# On_Board_Computer.net
KiCad netlist of a schematic drawn in EAGLE
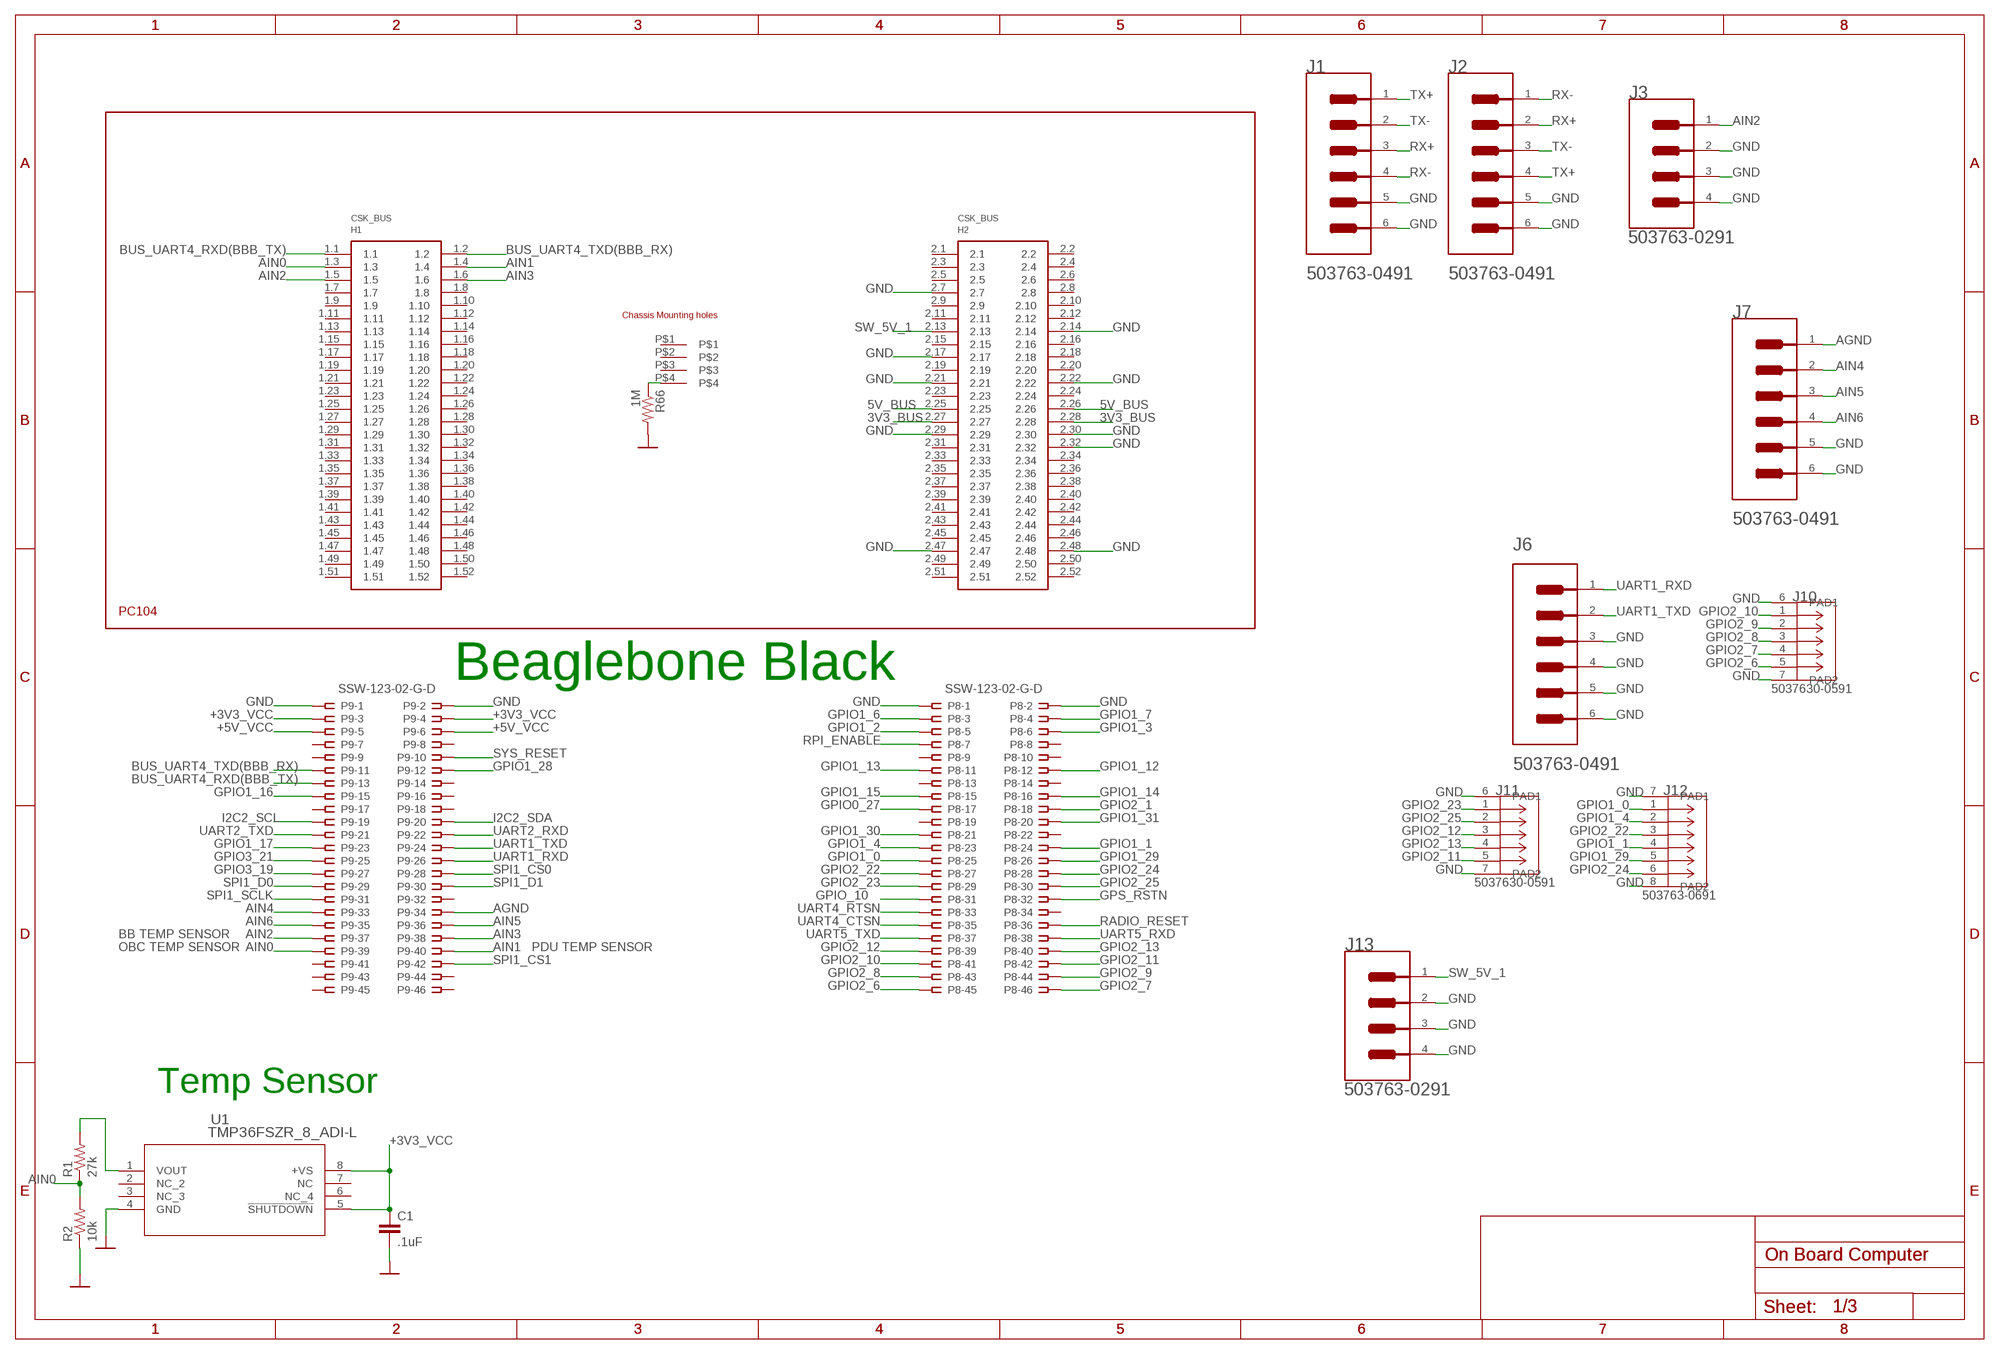
[diagram p0: schematic, sheet 1]
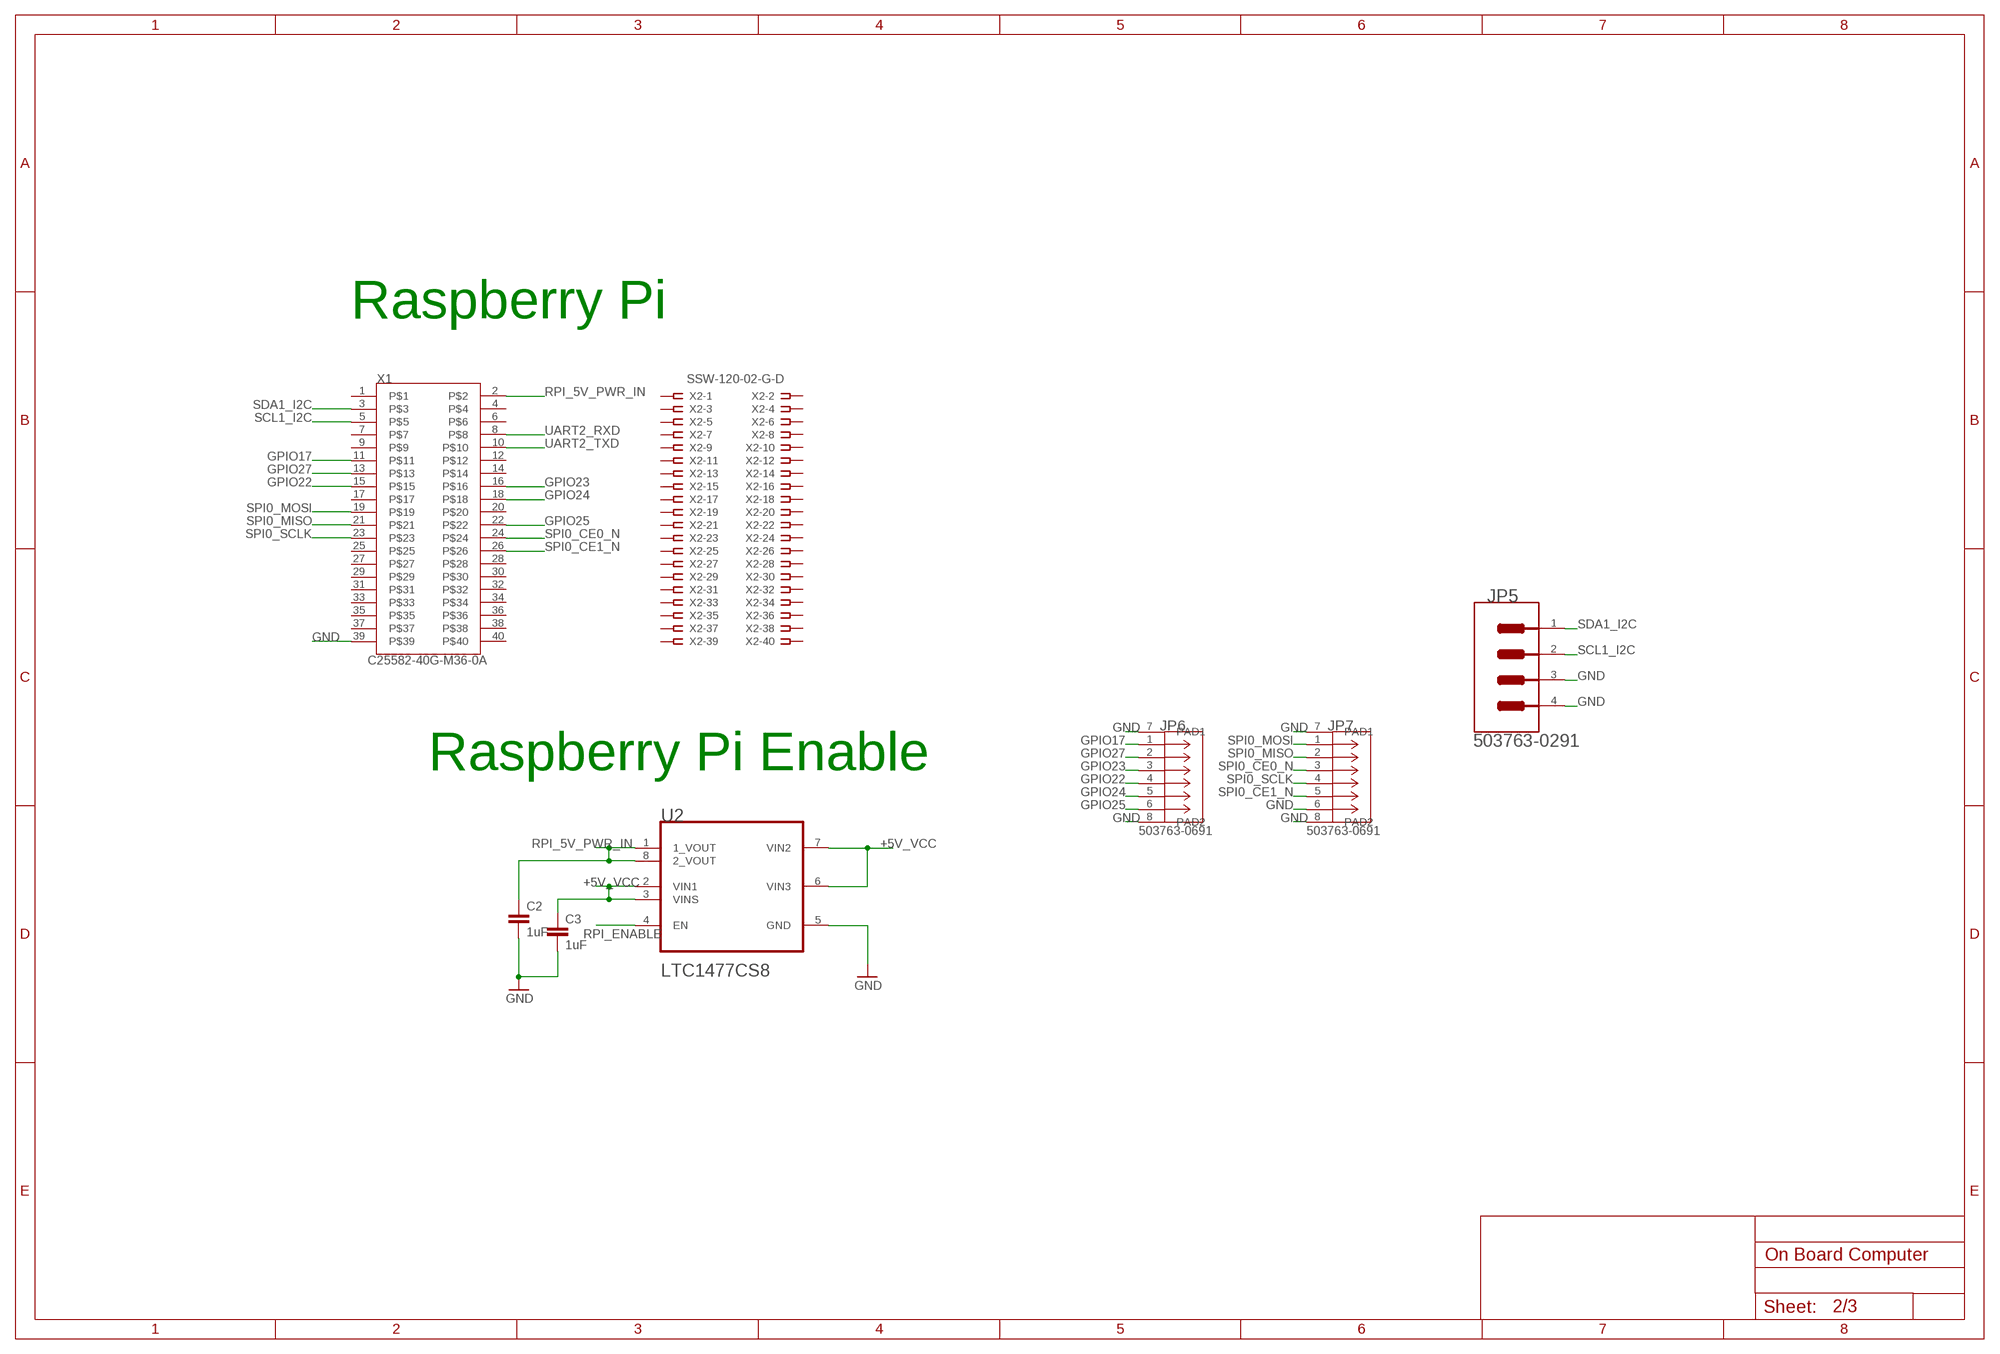
[diagram p1: schematic, sheet 2]
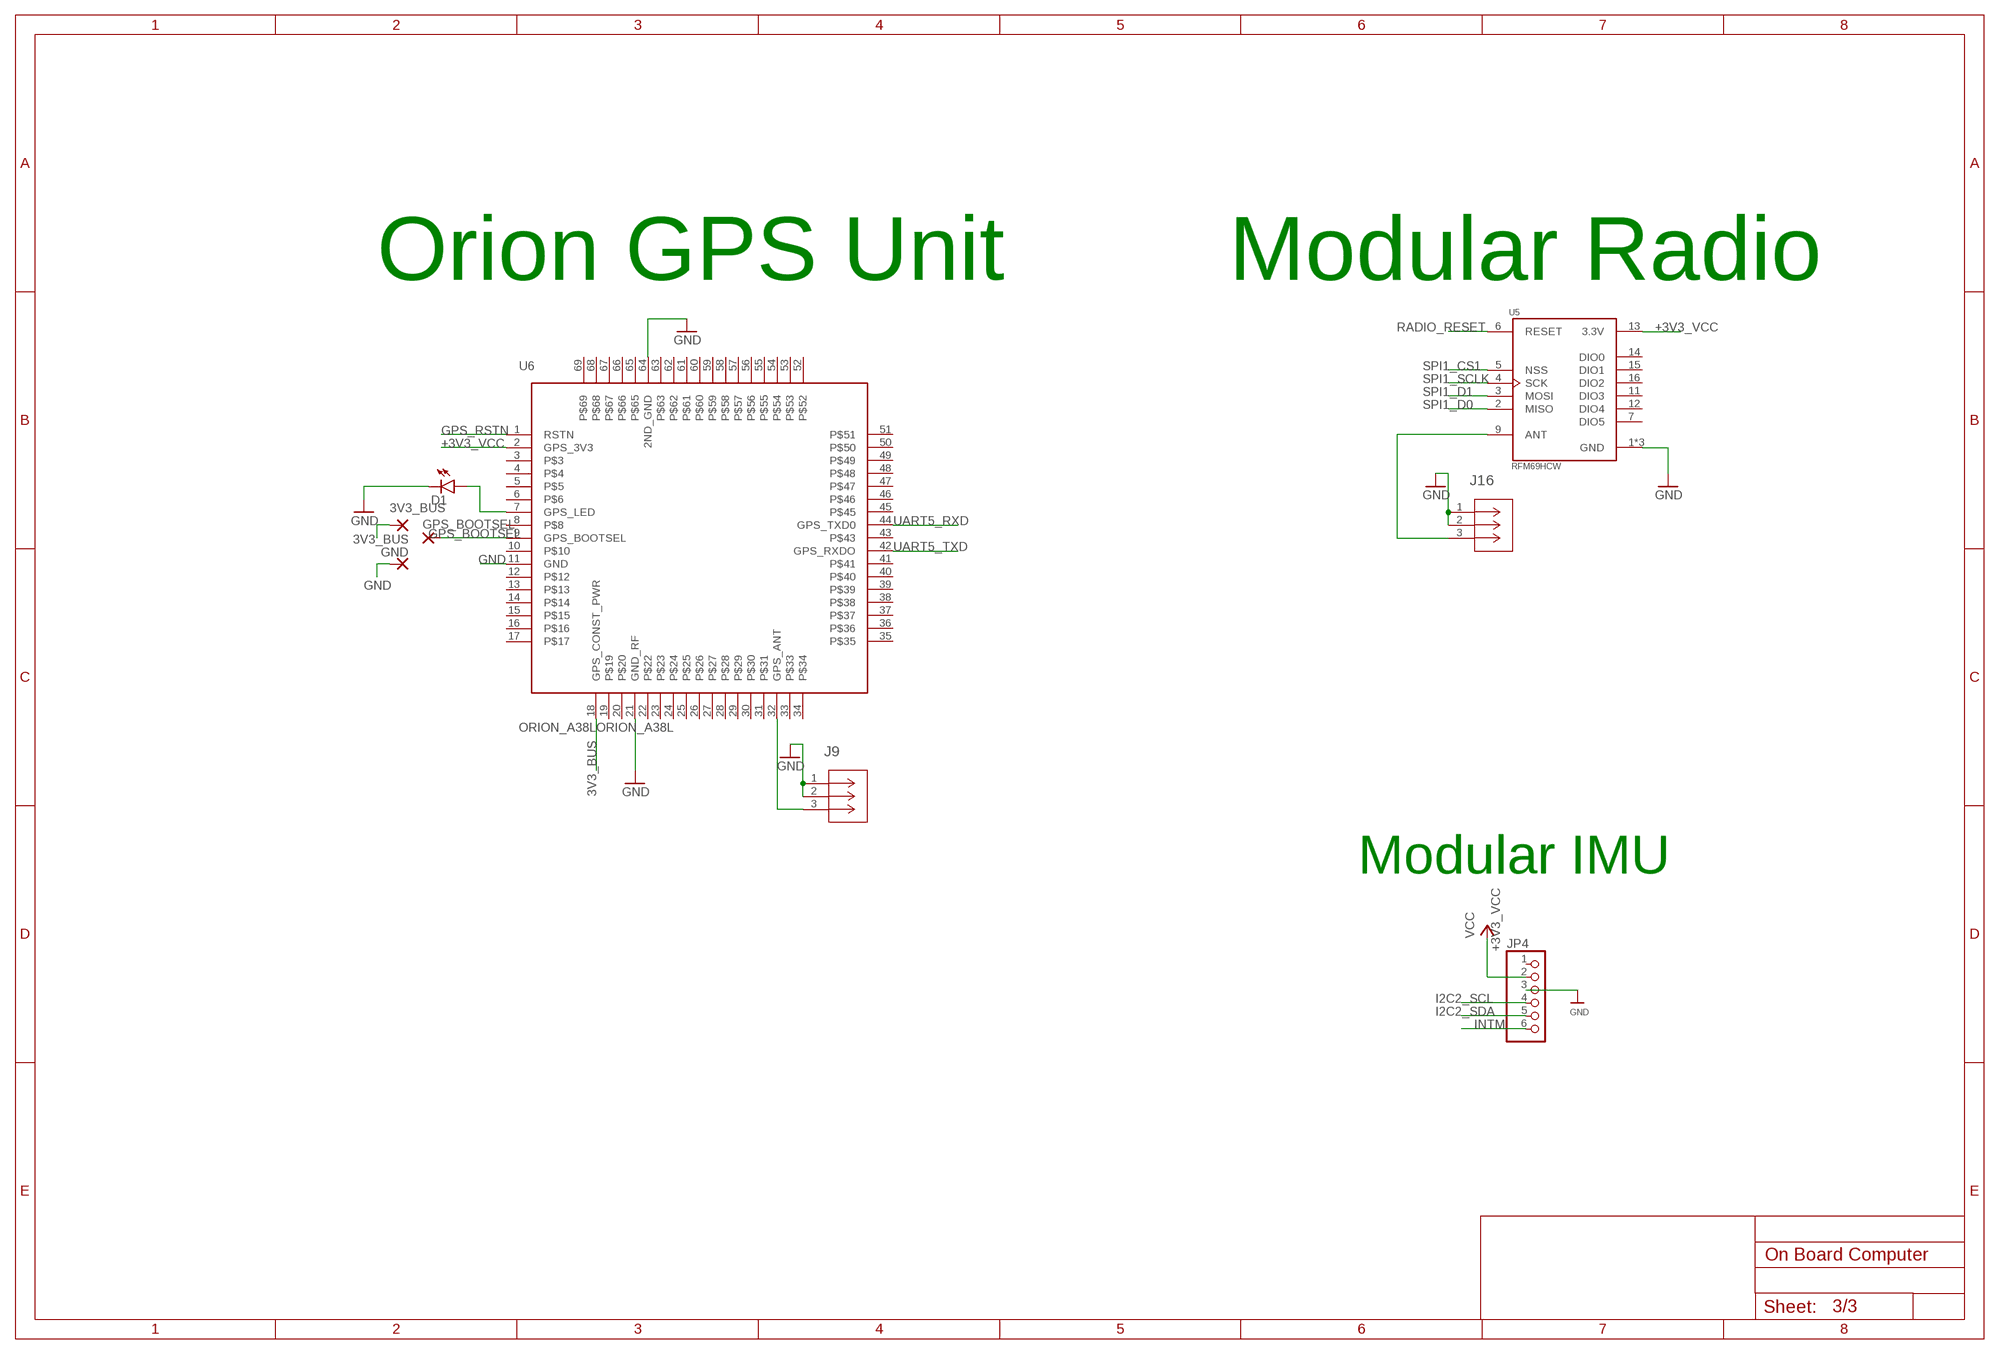
[diagram p2: schematic, sheet 3]

(export (version "E")
  (design (tool "Eeschema 10.0.6"))
  (components
    (comp (ref "3V3_BUS")
      (value "1,6/0,9")
      (footprint "eagle-import:1,6_0,9")
      (libsource (lib "eagle-import") (part "1,6/0,9"))
    )
    (comp (ref "D1")
      (value "LEDCHIP-LED0603")
      (footprint "eagle-import:CHIP-LED0603")
      (libsource (lib "eagle-import") (part "LEDCHIP-LED0603"))
    )
    (comp (ref "GND")
      (value "GND")
      (footprint "eagle-import:1,6_0,9")
      (libsource (lib "eagle-import") (part "1,6/0,9"))
    )
    (comp (ref "GPS_BOOTSEL")
      (value "1,6/0,9")
      (footprint "eagle-import:1,6_0,9")
      (libsource (lib "eagle-import") (part "1,6/0,9"))
    )
    (comp (ref "J9")
      (value "U.FL-R-SMT-1(01)")
      (footprint "eagle-import:CONN_-SMT-1(01)")
      (fields (field (name "COPYRIGHT") "Copyright (C) 2018 Accelerated Designs. All rights reserved"))
      (libsource (lib "eagle-import") (part "U.FL-R-SMT-1(01)"))
    )
    (comp (ref "J16")
      (value "U.FL-R-SMT-1(01)")
      (footprint "eagle-import:CONN_-SMT-1(01)")
      (fields (field (name "COPYRIGHT") "Copyright (C) 2018 Accelerated Designs. All rights reserved"))
      (libsource (lib "eagle-import") (part "U.FL-R-SMT-1(01)"))
    )
    (comp (ref "JP4")
      (value "HEADER-1X670MIL")
      (footprint "eagle-import:1X06_ROUND_70")
      (libsource (lib "eagle-import") (part "HEADER-1X670MIL"))
    )
    (comp (ref "U5")
      (value "RFM69HCW")
      (footprint "eagle-import:RFM69HCW")
      (fields (field (name "MF") "HOPERF") (field (name "MP") "RFM69HCW-315S2"))
      (libsource (lib "eagle-import") (part "RFM69HCW"))
    )
    (comp (ref "U6")
      (value "ORION_A38LORION_A38L")
      (footprint "eagle-import:ORION_A38L")
      (libsource (lib "eagle-import") (part "ORION_A38LORION_A38L"))
    )
    (comp (ref "C2")
      (value "1uF")
      (footprint "eagle-import:0805")
      (libsource (lib "eagle-import") (part "CAP0805"))
    )
    (comp (ref "C3")
      (value "1uF")
      (footprint "eagle-import:0805")
      (libsource (lib "eagle-import") (part "CAP0805"))
    )
    (comp (ref "JP5")
      (value "MOLEX_503763-0291MOLEX_503763-0291_0_0")
      (footprint "eagle-import:MOLEX_503763-0291_0")
      (fields
        (field (name "DIGIKEY_PART_NUMBER") "WM10654CT-ND")
        (field (name "MF") "Molex")
        (field (name "MOUSER_PART_NUMBER") "538-503763-0291")
      )
      (libsource (lib "eagle-import") (part "MOLEX_503763-0291MOLEX_503763-0291_0_0"))
    )
    (comp (ref "JP6")
      (value "503763-0691")
      (footprint "eagle-import:CONN_503763-0691_MOL")
      (fields (field (name "COPYRIGHT") "Copyright (C) 2018 Accelerated Designs. All rights reserved"))
      (libsource (lib "eagle-import") (part "503763-0691"))
    )
    (comp (ref "JP7")
      (value "503763-0691")
      (footprint "eagle-import:CONN_503763-0691_MOL")
      (fields (field (name "COPYRIGHT") "Copyright (C) 2018 Accelerated Designs. All rights reserved"))
      (libsource (lib "eagle-import") (part "503763-0691"))
    )
    (comp (ref "U2")
      (value "LTC1477CS8LINEAR_TECHNOLOGY_LTC1477CS8_0_2")
      (footprint "eagle-import:LINEAR_TECHNOLOGY_LTC1477CS8_2")
      (fields (field (name "MF") "Linear Technology") (field (name "MPN") "LTC1477CS8"))
      (libsource (lib "eagle-import") (part "LTC1477CS8LINEAR_TECHNOLOGY_LTC1477CS8_0_2"))
    )
    (comp (ref "X1")
      (value "C25582-40G-M36-0A")
      (footprint "eagle-import:ADAFRUIT_C25582-40G-M36-0A_0")
      (libsource (lib "eagle-import") (part "C25582-40G-M36-0A"))
    )
    (comp (ref "X2")
      (value "SSW-120-02-G-D")
      (footprint "eagle-import:SSW-120-02-G-D")
      (fields (field (name "MF") "Samtec Inc."))
      (libsource (lib "eagle-import") (part "SSW-120-02-G-D"))
    )
    (comp (ref "C1")
      (value ".1uF")
      (footprint "eagle-import:0805")
      (libsource (lib "eagle-import") (part "CAP0805"))
    )
    (comp (ref "H1")
      (value "PC104_WCONN")
      (footprint "eagle-import:PC104_WCONN")
      (libsource (lib "eagle-import") (part "PC104_WCONN"))
    )
    (comp (ref "J1")
      (value "MOLEX_503763-0491MOLEX_503763-0491_0_0")
      (footprint "eagle-import:MOLEX_503763-0491_0")
      (fields
        (field (name "DIGIKEY_PART_NUMBER") "WM10655CT-ND")
        (field (name "MF") "Molex")
        (field (name "MOUSER_PART_NUMBER") "538-503763-0491")
      )
      (libsource (lib "eagle-import") (part "MOLEX_503763-0491MOLEX_503763-0491_0_0"))
    )
    (comp (ref "J2")
      (value "MOLEX_503763-0491MOLEX_503763-0491_0_0")
      (footprint "eagle-import:MOLEX_503763-0491_0")
      (fields
        (field (name "DIGIKEY_PART_NUMBER") "WM10655CT-ND")
        (field (name "MF") "Molex")
        (field (name "MOUSER_PART_NUMBER") "538-503763-0491")
      )
      (libsource (lib "eagle-import") (part "MOLEX_503763-0491MOLEX_503763-0491_0_0"))
    )
    (comp (ref "J3")
      (value "MOLEX_503763-0291MOLEX_503763-0291_0_0")
      (footprint "eagle-import:MOLEX_503763-0291_0")
      (fields
        (field (name "DIGIKEY_PART_NUMBER") "WM10654CT-ND")
        (field (name "MF") "Molex")
        (field (name "MOUSER_PART_NUMBER") "538-503763-0291")
      )
      (libsource (lib "eagle-import") (part "MOLEX_503763-0291MOLEX_503763-0291_0_0"))
    )
    (comp (ref "J6")
      (value "MOLEX_503763-0491MOLEX_503763-0491_0_0")
      (footprint "eagle-import:MOLEX_503763-0491_0")
      (fields
        (field (name "DIGIKEY_PART_NUMBER") "WM10655CT-ND")
        (field (name "MF") "Molex")
        (field (name "MOUSER_PART_NUMBER") "538-503763-0491")
      )
      (libsource (lib "eagle-import") (part "MOLEX_503763-0491MOLEX_503763-0491_0_0"))
    )
    (comp (ref "J7")
      (value "MOLEX_503763-0491MOLEX_503763-0491_0_0")
      (footprint "eagle-import:MOLEX_503763-0491_0")
      (fields
        (field (name "DIGIKEY_PART_NUMBER") "WM10655CT-ND")
        (field (name "MF") "Molex")
        (field (name "MOUSER_PART_NUMBER") "538-503763-0491")
      )
      (libsource (lib "eagle-import") (part "MOLEX_503763-0491MOLEX_503763-0491_0_0"))
    )
    (comp (ref "J10")
      (value "503763-0591")
      (footprint "eagle-import:CONN_5037630591_MOL")
      (fields (field (name "COPYRIGHT") "Copyright (C) 2018 Accelerated Designs. All rights reserved"))
      (libsource (lib "eagle-import") (part "503763-0591"))
    )
    (comp (ref "J11")
      (value "503763-0591")
      (footprint "eagle-import:CONN_5037630591_MOL")
      (fields (field (name "COPYRIGHT") "Copyright (C) 2018 Accelerated Designs. All rights reserved"))
      (libsource (lib "eagle-import") (part "503763-0591"))
    )
    (comp (ref "J12")
      (value "503763-0691")
      (footprint "eagle-import:CONN_503763-0691_MOL")
      (fields (field (name "COPYRIGHT") "Copyright (C) 2018 Accelerated Designs. All rights reserved"))
      (libsource (lib "eagle-import") (part "503763-0691"))
    )
    (comp (ref "J13")
      (value "MOLEX_503763-0291MOLEX_503763-0291_0_0")
      (footprint "eagle-import:MOLEX_503763-0291_0")
      (fields
        (field (name "DIGIKEY_PART_NUMBER") "WM10654CT-ND")
        (field (name "MF") "Molex")
        (field (name "MOUSER_PART_NUMBER") "538-503763-0291")
      )
      (libsource (lib "eagle-import") (part "MOLEX_503763-0291MOLEX_503763-0291_0_0"))
    )
    (comp (ref "P8")
      (value "SSW-123-02-G-D")
      (footprint "eagle-import:SSW-123-02-G-D")
      (fields (field (name "MF") "Samtec Inc."))
      (libsource (lib "eagle-import") (part "SSW-123-02-G-D"))
    )
    (comp (ref "P9")
      (value "SSW-123-02-G-D")
      (footprint "eagle-import:SSW-123-02-G-D")
      (fields (field (name "MF") "Samtec Inc."))
      (libsource (lib "eagle-import") (part "SSW-123-02-G-D"))
    )
    (comp (ref "R1")
      (value "27k")
      (footprint "eagle-import:0805")
      (libsource (lib "eagle-import") (part "RESISTOR0805-RES"))
    )
    (comp (ref "R2")
      (value "10k")
      (footprint "eagle-import:0805")
      (libsource (lib "eagle-import") (part "RESISTOR0805-RES"))
    )
    (comp (ref "R66")
      (value "1M")
      (footprint "eagle-import:0805")
      (libsource (lib "eagle-import") (part "RESISTOR0805-RES"))
    )
    (comp (ref "U1")
      (value "TMP36FSZR_8_ADI-L")
      (footprint "eagle-import:R_8_ADI-L")
      (fields
        (field (name "MANUFACTURER_PART_NUMBER") "TMP36FSZ")
        (field (name "COPYRIGHT") "Copyright (C) 2021 Ultra Librarian. All rights reserved.")
      )
      (libsource (lib "eagle-import") (part "TMP36FSZR_8_ADI-L"))
    )
  )
  (nets
    (net (code "1") (name "+3V3_VCC") (class "Default")
      (node (ref "C1") (pin "1") (pinfunction "1_1") (pintype "passive"))
      (node (ref "JP4") (pin "2") (pinfunction "2_2") (pintype "passive"))
      (node (ref "P9") (pin "3") (pinfunction "1_3") (pintype "passive"))
      (node (ref "P9") (pin "4") (pinfunction "1_4") (pintype "passive"))
      (node (ref "U1") (pin "5") (pinfunction "~{SHUTDOWN}_5") (pintype "passive"))
      (node (ref "U1") (pin "8") (pinfunction "+VS_8") (pintype "power_in"))
      (node (ref "U5") (pin "13") (pinfunction "3.3V_13") (pintype "power_in"))
      (node (ref "U6") (pin "2") (pinfunction "GPS_3V3_2") (pintype "bidirectional"))
    )
    (net (code "2") (name "+5V_VCC") (class "Default")
      (node (ref "C3") (pin "1") (pinfunction "1_1") (pintype "passive"))
      (node (ref "P9") (pin "5") (pinfunction "1_5") (pintype "passive"))
      (node (ref "P9") (pin "6") (pinfunction "1_6") (pintype "passive"))
      (node (ref "U2") (pin "2") (pinfunction "VIN1_2") (pintype "power_in"))
      (node (ref "U2") (pin "3") (pinfunction "VINS_3") (pintype "power_in"))
      (node (ref "U2") (pin "6") (pinfunction "VIN3_6") (pintype "power_in"))
      (node (ref "U2") (pin "7") (pinfunction "VIN2_7") (pintype "power_in"))
    )
    (net (code "3") (name "3V3_BUS") (class "Default")
      (node (ref "3V3_BUS") (pin "1") (pinfunction "P_1") (pintype "passive"))
      (node (ref "H1") (pin "2.27") (pinfunction "2.27_2.27") (pintype "bidirectional"))
      (node (ref "H1") (pin "2.28") (pinfunction "2.28_2.28") (pintype "bidirectional"))
      (node (ref "U6") (pin "18") (pinfunction "GPS_CONST_PWR_18") (pintype "bidirectional"))
    )
    (net (code "4") (name "5V_BUS") (class "Default")
      (node (ref "H1") (pin "2.25") (pinfunction "2.25_2.25") (pintype "bidirectional"))
      (node (ref "H1") (pin "2.26") (pinfunction "2.26_2.26") (pintype "bidirectional"))
    )
    (net (code "5") (name "AGND") (class "Default")
      (node (ref "J7") (pin "1") (pinfunction "1_1") (pintype "passive"))
      (node (ref "P9") (pin "34") (pinfunction "1_34") (pintype "passive"))
    )
    (net (code "6") (name "AIN0") (class "Default")
      (node (ref "H1") (pin "1.3") (pinfunction "1.3_1.3") (pintype "bidirectional"))
      (node (ref "P9") (pin "39") (pinfunction "1_39") (pintype "passive"))
      (node (ref "R1") (pin "1") (pinfunction "1_1") (pintype "passive"))
      (node (ref "R2") (pin "2") (pinfunction "2_2") (pintype "passive"))
    )
    (net (code "7") (name "AIN1") (class "Default")
      (node (ref "H1") (pin "1.4") (pinfunction "1.4_1.4") (pintype "bidirectional"))
      (node (ref "P9") (pin "40") (pinfunction "1_40") (pintype "passive"))
    )
    (net (code "8") (name "AIN2") (class "Default")
      (node (ref "H1") (pin "1.5") (pinfunction "1.5_1.5") (pintype "bidirectional"))
      (node (ref "J3") (pin "1") (pinfunction "1_1") (pintype "bidirectional"))
      (node (ref "P9") (pin "37") (pinfunction "1_37") (pintype "passive"))
    )
    (net (code "9") (name "AIN3") (class "Default")
      (node (ref "H1") (pin "1.6") (pinfunction "1.6_1.6") (pintype "bidirectional"))
      (node (ref "P9") (pin "38") (pinfunction "1_38") (pintype "passive"))
    )
    (net (code "10") (name "AIN4") (class "Default")
      (node (ref "J7") (pin "2") (pinfunction "2_2") (pintype "passive"))
      (node (ref "P9") (pin "33") (pinfunction "1_33") (pintype "passive"))
    )
    (net (code "11") (name "AIN5") (class "Default")
      (node (ref "J7") (pin "3") (pinfunction "3_3") (pintype "passive"))
      (node (ref "P9") (pin "36") (pinfunction "1_36") (pintype "passive"))
    )
    (net (code "12") (name "AIN6") (class "Default")
      (node (ref "J7") (pin "4") (pinfunction "4_4") (pintype "passive"))
      (node (ref "P9") (pin "35") (pinfunction "1_35") (pintype "passive"))
    )
    (net (code "13") (name "BUS_UART4_RXD(BBB_TX)") (class "Default")
      (node (ref "H1") (pin "1.1") (pinfunction "1.1_1.1") (pintype "bidirectional"))
      (node (ref "P9") (pin "13") (pinfunction "1_13") (pintype "passive"))
    )
    (net (code "14") (name "BUS_UART4_TXD(BBB_RX)") (class "Default")
      (node (ref "H1") (pin "1.2") (pinfunction "1.2_1.2") (pintype "bidirectional"))
      (node (ref "P9") (pin "11") (pinfunction "1_11") (pintype "passive"))
    )
    (net (code "15") (name "GND") (class "Default")
      (node (ref "C1") (pin "2") (pinfunction "2_2") (pintype "passive"))
      (node (ref "C2") (pin "2") (pinfunction "2_2") (pintype "passive"))
      (node (ref "C3") (pin "2") (pinfunction "2_2") (pintype "passive"))
      (node (ref "D1") (pin "C") (pinfunction "C_C") (pintype "passive"))
      (node (ref "GND") (pin "1") (pinfunction "P_1") (pintype "passive"))
      (node (ref "H1") (pin "2.14") (pinfunction "2.14_2.14") (pintype "bidirectional"))
      (node (ref "H1") (pin "2.17") (pinfunction "2.17_2.17") (pintype "bidirectional"))
      (node (ref "H1") (pin "2.21") (pinfunction "2.21_2.21") (pintype "bidirectional"))
      (node (ref "H1") (pin "2.22") (pinfunction "2.22_2.22") (pintype "bidirectional"))
      (node (ref "H1") (pin "2.29") (pinfunction "2.29_2.29") (pintype "bidirectional"))
      (node (ref "H1") (pin "2.30") (pinfunction "2.30_2.30") (pintype "bidirectional"))
      (node (ref "H1") (pin "2.32") (pinfunction "2.32_2.32") (pintype "bidirectional"))
      (node (ref "H1") (pin "2.47") (pinfunction "2.47_2.47") (pintype "bidirectional"))
      (node (ref "H1") (pin "2.48") (pinfunction "2.48_2.48") (pintype "bidirectional"))
      (node (ref "H1") (pin "2.7") (pinfunction "2.7_2.7") (pintype "bidirectional"))
      (node (ref "J1") (pin "5") (pinfunction "MNT_1_5") (pintype "passive"))
      (node (ref "J1") (pin "6") (pinfunction "MNT_2_6") (pintype "passive"))
      (node (ref "J10") (pin "6") (pinfunction "PAD1_6") (pintype "bidirectional"))
      (node (ref "J10") (pin "7") (pinfunction "PAD2_7") (pintype "bidirectional"))
      (node (ref "J11") (pin "6") (pinfunction "PAD1_6") (pintype "bidirectional"))
      (node (ref "J11") (pin "7") (pinfunction "PAD2_7") (pintype "bidirectional"))
      (node (ref "J12") (pin "7") (pinfunction "PAD1_7") (pintype "bidirectional"))
      (node (ref "J12") (pin "8") (pinfunction "PAD2_8") (pintype "bidirectional"))
      (node (ref "J13") (pin "2") (pinfunction "2_2") (pintype "bidirectional"))
      (node (ref "J13") (pin "3") (pinfunction "MNT_1_3") (pintype "bidirectional"))
      (node (ref "J13") (pin "4") (pinfunction "MNT_2_4") (pintype "bidirectional"))
      (node (ref "J16") (pin "1") (pinfunction "1_1") (pintype "passive"))
      (node (ref "J16") (pin "2") (pinfunction "2_2") (pintype "passive"))
      (node (ref "J2") (pin "5") (pinfunction "MNT_1_5") (pintype "passive"))
      (node (ref "J2") (pin "6") (pinfunction "MNT_2_6") (pintype "passive"))
      (node (ref "J3") (pin "2") (pinfunction "2_2") (pintype "bidirectional"))
      (node (ref "J3") (pin "3") (pinfunction "MNT_1_3") (pintype "bidirectional"))
      (node (ref "J3") (pin "4") (pinfunction "MNT_2_4") (pintype "bidirectional"))
      (node (ref "J6") (pin "3") (pinfunction "3_3") (pintype "passive"))
      (node (ref "J6") (pin "4") (pinfunction "4_4") (pintype "passive"))
      (node (ref "J6") (pin "5") (pinfunction "MNT_1_5") (pintype "passive"))
      (node (ref "J6") (pin "6") (pinfunction "MNT_2_6") (pintype "passive"))
      (node (ref "J7") (pin "5") (pinfunction "MNT_1_5") (pintype "passive"))
      (node (ref "J7") (pin "6") (pinfunction "MNT_2_6") (pintype "passive"))
      (node (ref "J9") (pin "1") (pinfunction "1_1") (pintype "passive"))
      (node (ref "J9") (pin "2") (pinfunction "2_2") (pintype "passive"))
      (node (ref "JP4") (pin "3") (pinfunction "3_3") (pintype "passive"))
      (node (ref "JP5") (pin "3") (pinfunction "MNT_1_3") (pintype "bidirectional"))
      (node (ref "JP5") (pin "4") (pinfunction "MNT_2_4") (pintype "bidirectional"))
      (node (ref "JP6") (pin "7") (pinfunction "PAD1_7") (pintype "bidirectional"))
      (node (ref "JP6") (pin "8") (pinfunction "PAD2_8") (pintype "bidirectional"))
      (node (ref "JP7") (pin "6") (pinfunction "6_6") (pintype "passive"))
      (node (ref "JP7") (pin "7") (pinfunction "PAD1_7") (pintype "bidirectional"))
      (node (ref "JP7") (pin "8") (pinfunction "PAD2_8") (pintype "bidirectional"))
      (node (ref "P8") (pin "1") (pinfunction "1_1") (pintype "passive"))
      (node (ref "P8") (pin "2") (pinfunction "1_2") (pintype "passive"))
      (node (ref "P9") (pin "1") (pinfunction "1_1") (pintype "passive"))
      (node (ref "P9") (pin "2") (pinfunction "1_2") (pintype "passive"))
      (node (ref "R2") (pin "1") (pinfunction "1_1") (pintype "passive"))
      (node (ref "R66") (pin "2") (pinfunction "2_2") (pintype "passive"))
      (node (ref "U1") (pin "4") (pinfunction "GND_4") (pintype "passive"))
      (node (ref "U2") (pin "5") (pinfunction "GND_5") (pintype "power_in"))
      (node (ref "U5") (pin "1") (pinfunction "GND_1") (pintype "power_in"))
      (node (ref "U5") (pin "10") (pinfunction "GND_10") (pintype "power_in"))
      (node (ref "U5") (pin "8") (pinfunction "GND_8") (pintype "power_in"))
      (node (ref "U6") (pin "11") (pinfunction "GND_11") (pintype "bidirectional"))
      (node (ref "U6") (pin "21") (pinfunction "GND_RF_21") (pintype "bidirectional"))
      (node (ref "U6") (pin "64") (pinfunction "2ND_GND_64") (pintype "bidirectional"))
      (node (ref "X1") (pin "39") (pinfunction "P$39_39") (pintype "bidirectional"))
    )
    (net (code "16") (name "GPIO0_27") (class "Default")
      (node (ref "P8") (pin "17") (pinfunction "1_17") (pintype "passive"))
    )
    (net (code "17") (name "GPIO1_0") (class "Default")
      (node (ref "J12") (pin "1") (pinfunction "1_1") (pintype "passive"))
      (node (ref "P8") (pin "25") (pinfunction "1_25") (pintype "passive"))
    )
    (net (code "18") (name "GPIO1_1") (class "Default")
      (node (ref "J12") (pin "4") (pinfunction "4_4") (pintype "passive"))
      (node (ref "P8") (pin "24") (pinfunction "1_24") (pintype "passive"))
    )
    (net (code "19") (name "GPIO1_2") (class "Default")
      (node (ref "P8") (pin "5") (pinfunction "1_5") (pintype "passive"))
    )
    (net (code "20") (name "GPIO1_3") (class "Default")
      (node (ref "P8") (pin "6") (pinfunction "1_6") (pintype "passive"))
    )
    (net (code "21") (name "GPIO1_4") (class "Default")
      (node (ref "J12") (pin "2") (pinfunction "2_2") (pintype "passive"))
      (node (ref "P8") (pin "23") (pinfunction "1_23") (pintype "passive"))
    )
    (net (code "22") (name "GPIO1_6") (class "Default")
      (node (ref "P8") (pin "3") (pinfunction "1_3") (pintype "passive"))
    )
    (net (code "23") (name "GPIO1_7") (class "Default")
      (node (ref "P8") (pin "4") (pinfunction "1_4") (pintype "passive"))
    )
    (net (code "24") (name "GPIO1_12") (class "Default")
      (node (ref "P8") (pin "12") (pinfunction "1_12") (pintype "passive"))
    )
    (net (code "25") (name "GPIO1_13") (class "Default")
      (node (ref "P8") (pin "11") (pinfunction "1_11") (pintype "passive"))
    )
    (net (code "26") (name "GPIO1_14") (class "Default")
      (node (ref "P8") (pin "16") (pinfunction "1_16") (pintype "passive"))
    )
    (net (code "27") (name "GPIO1_15") (class "Default")
      (node (ref "P8") (pin "15") (pinfunction "1_15") (pintype "passive"))
    )
    (net (code "28") (name "GPIO1_16") (class "Default")
      (node (ref "P9") (pin "15") (pinfunction "1_15") (pintype "passive"))
    )
    (net (code "29") (name "GPIO1_17") (class "Default")
      (node (ref "P9") (pin "23") (pinfunction "1_23") (pintype "passive"))
    )
    (net (code "30") (name "GPIO1_28") (class "Default")
      (node (ref "P9") (pin "12") (pinfunction "1_12") (pintype "passive"))
    )
    (net (code "31") (name "GPIO1_29") (class "Default")
      (node (ref "J12") (pin "5") (pinfunction "5_5") (pintype "passive"))
      (node (ref "P8") (pin "26") (pinfunction "1_26") (pintype "passive"))
    )
    (net (code "32") (name "GPIO1_30") (class "Default")
      (node (ref "P8") (pin "21") (pinfunction "1_21") (pintype "passive"))
    )
    (net (code "33") (name "GPIO1_31") (class "Default")
      (node (ref "P8") (pin "20") (pinfunction "1_20") (pintype "passive"))
    )
    (net (code "34") (name "GPIO2_1") (class "Default")
      (node (ref "P8") (pin "18") (pinfunction "1_18") (pintype "passive"))
    )
    (net (code "35") (name "GPIO2_6") (class "Default")
      (node (ref "J10") (pin "5") (pinfunction "5_5") (pintype "passive"))
      (node (ref "P8") (pin "45") (pinfunction "1_45") (pintype "passive"))
    )
    (net (code "36") (name "GPIO2_7") (class "Default")
      (node (ref "J10") (pin "4") (pinfunction "4_4") (pintype "passive"))
      (node (ref "P8") (pin "46") (pinfunction "1_46") (pintype "passive"))
    )
    (net (code "37") (name "GPIO2_8") (class "Default")
      (node (ref "J10") (pin "3") (pinfunction "3_3") (pintype "passive"))
      (node (ref "P8") (pin "43") (pinfunction "1_43") (pintype "passive"))
    )
    (net (code "38") (name "GPIO2_9") (class "Default")
      (node (ref "J10") (pin "2") (pinfunction "2_2") (pintype "passive"))
      (node (ref "P8") (pin "44") (pinfunction "1_44") (pintype "passive"))
    )
    (net (code "39") (name "GPIO2_10") (class "Default")
      (node (ref "J10") (pin "1") (pinfunction "1_1") (pintype "passive"))
      (node (ref "P8") (pin "41") (pinfunction "1_41") (pintype "passive"))
    )
    (net (code "40") (name "GPIO2_11") (class "Default")
      (node (ref "J11") (pin "5") (pinfunction "5_5") (pintype "passive"))
      (node (ref "P8") (pin "42") (pinfunction "1_42") (pintype "passive"))
    )
    (net (code "41") (name "GPIO2_12") (class "Default")
      (node (ref "J11") (pin "3") (pinfunction "3_3") (pintype "passive"))
      (node (ref "P8") (pin "39") (pinfunction "1_39") (pintype "passive"))
    )
    (net (code "42") (name "GPIO2_13") (class "Default")
      (node (ref "J11") (pin "4") (pinfunction "4_4") (pintype "passive"))
      (node (ref "P8") (pin "40") (pinfunction "1_40") (pintype "passive"))
    )
    (net (code "43") (name "GPIO2_22") (class "Default")
      (node (ref "J12") (pin "3") (pinfunction "3_3") (pintype "passive"))
      (node (ref "P8") (pin "27") (pinfunction "1_27") (pintype "passive"))
    )
    (net (code "44") (name "GPIO2_23") (class "Default")
      (node (ref "J11") (pin "1") (pinfunction "1_1") (pintype "passive"))
      (node (ref "P8") (pin "29") (pinfunction "1_29") (pintype "passive"))
    )
    (net (code "45") (name "GPIO2_24") (class "Default")
      (node (ref "J12") (pin "6") (pinfunction "6_6") (pintype "passive"))
      (node (ref "P8") (pin "28") (pinfunction "1_28") (pintype "passive"))
    )
    (net (code "46") (name "GPIO2_25") (class "Default")
      (node (ref "J11") (pin "2") (pinfunction "2_2") (pintype "passive"))
      (node (ref "P8") (pin "30") (pinfunction "1_30") (pintype "passive"))
    )
    (net (code "47") (name "GPIO3_19") (class "Default")
      (node (ref "P9") (pin "27") (pinfunction "1_27") (pintype "passive"))
    )
    (net (code "48") (name "GPIO3_21") (class "Default")
      (node (ref "P9") (pin "25") (pinfunction "1_25") (pintype "passive"))
    )
    (net (code "49") (name "GPIO17") (class "Default")
      (node (ref "JP6") (pin "1") (pinfunction "1_1") (pintype "passive"))
      (node (ref "X1") (pin "11") (pinfunction "P$11_11") (pintype "bidirectional"))
    )
    (net (code "50") (name "GPIO22") (class "Default")
      (node (ref "JP6") (pin "4") (pinfunction "4_4") (pintype "passive"))
      (node (ref "X1") (pin "15") (pinfunction "P$15_15") (pintype "bidirectional"))
    )
    (net (code "51") (name "GPIO23") (class "Default")
      (node (ref "JP6") (pin "3") (pinfunction "3_3") (pintype "passive"))
      (node (ref "X1") (pin "16") (pinfunction "P$16_16") (pintype "bidirectional"))
    )
    (net (code "52") (name "GPIO24") (class "Default")
      (node (ref "JP6") (pin "5") (pinfunction "5_5") (pintype "passive"))
      (node (ref "X1") (pin "18") (pinfunction "P$18_18") (pintype "bidirectional"))
    )
    (net (code "53") (name "GPIO25") (class "Default")
      (node (ref "JP6") (pin "6") (pinfunction "6_6") (pintype "passive"))
      (node (ref "X1") (pin "22") (pinfunction "P$22_22") (pintype "bidirectional"))
    )
    (net (code "54") (name "GPIO27") (class "Default")
      (node (ref "JP6") (pin "2") (pinfunction "2_2") (pintype "passive"))
      (node (ref "X1") (pin "13") (pinfunction "P$13_13") (pintype "bidirectional"))
    )
    (net (code "55") (name "GPIO_10") (class "Default")
      (node (ref "P8") (pin "31") (pinfunction "1_31") (pintype "passive"))
    )
    (net (code "56") (name "GPS_BOOTSEL") (class "Default")
      (node (ref "GPS_BOOTSEL") (pin "1") (pinfunction "P_1") (pintype "passive"))
      (node (ref "U6") (pin "9") (pinfunction "GPS_BOOTSEL_9") (pintype "bidirectional"))
    )
    (net (code "57") (name "GPS_RSTN") (class "Default")
      (node (ref "P8") (pin "32") (pinfunction "1_32") (pintype "passive"))
      (node (ref "U6") (pin "1") (pinfunction "RSTN_1") (pintype "bidirectional"))
    )
    (net (code "58") (name "I2C2_SCL") (class "Default")
      (node (ref "JP4") (pin "4") (pinfunction "4_4") (pintype "passive"))
      (node (ref "P9") (pin "19") (pinfunction "1_19") (pintype "passive"))
    )
    (net (code "59") (name "I2C2_SDA") (class "Default")
      (node (ref "JP4") (pin "5") (pinfunction "5_5") (pintype "passive"))
      (node (ref "P9") (pin "20") (pinfunction "1_20") (pintype "passive"))
    )
    (net (code "60") (name "INTM") (class "Default")
      (node (ref "JP4") (pin "6") (pinfunction "6_6") (pintype "passive"))
    )
    (net (code "61") (name "Net-(H1-PadP$4)") (class "Default")
      (node (ref "H1") (pin "P$4") (pinfunction "P$4_P$4") (pintype "bidirectional"))
      (node (ref "R66") (pin "1") (pinfunction "1_1") (pintype "passive"))
    )
    (net (code "62") (name "Net-(U1-VOUT)") (class "Default")
      (node (ref "R1") (pin "2") (pinfunction "2_2") (pintype "passive"))
      (node (ref "U1") (pin "1") (pinfunction "VOUT_1") (pintype "output"))
    )
    (net (code "63") (name "Net-(U5-ANT)") (class "Default")
      (node (ref "J16") (pin "3") (pinfunction "3_3") (pintype "passive"))
      (node (ref "U5") (pin "9") (pinfunction "ANT_9") (pintype "bidirectional"))
    )
    (net (code "64") (name "Net-(U6-GPS_ANT)") (class "Default")
      (node (ref "J9") (pin "3") (pinfunction "3_3") (pintype "passive"))
      (node (ref "U6") (pin "32") (pinfunction "GPS_ANT_32") (pintype "bidirectional"))
    )
    (net (code "65") (name "Net-(U6-GPS_LED)") (class "Default")
      (node (ref "D1") (pin "A") (pinfunction "A_A") (pintype "passive"))
      (node (ref "U6") (pin "7") (pinfunction "GPS_LED_7") (pintype "bidirectional"))
    )
    (net (code "66") (name "RADIO_RESET") (class "Default")
      (node (ref "P8") (pin "36") (pinfunction "1_36") (pintype "passive"))
      (node (ref "U5") (pin "6") (pinfunction "RESET_6") (pintype "bidirectional"))
    )
    (net (code "67") (name "RPI_5V_PWR_IN") (class "Default")
      (node (ref "C2") (pin "1") (pinfunction "1_1") (pintype "passive"))
      (node (ref "U2") (pin "1") (pinfunction "1_VOUT_1") (pintype "power_in"))
      (node (ref "U2") (pin "8") (pinfunction "2_VOUT_8") (pintype "power_in"))
      (node (ref "X1") (pin "2") (pinfunction "P$2_2") (pintype "bidirectional"))
    )
    (net (code "68") (name "RPI_ENABLE") (class "Default")
      (node (ref "P8") (pin "7") (pinfunction "1_7") (pintype "passive"))
      (node (ref "U2") (pin "4") (pinfunction "EN_4") (pintype "input"))
    )
    (net (code "69") (name "RX+") (class "Default")
      (node (ref "J1") (pin "3") (pinfunction "3_3") (pintype "passive"))
      (node (ref "J2") (pin "2") (pinfunction "2_2") (pintype "passive"))
    )
    (net (code "70") (name "RX-") (class "Default")
      (node (ref "J1") (pin "4") (pinfunction "4_4") (pintype "passive"))
      (node (ref "J2") (pin "1") (pinfunction "1_1") (pintype "passive"))
    )
    (net (code "71") (name "SCL1_I2C") (class "Default")
      (node (ref "JP5") (pin "2") (pinfunction "2_2") (pintype "bidirectional"))
      (node (ref "X1") (pin "5") (pinfunction "P$5_5") (pintype "bidirectional"))
    )
    (net (code "72") (name "SDA1_I2C") (class "Default")
      (node (ref "JP5") (pin "1") (pinfunction "1_1") (pintype "bidirectional"))
      (node (ref "X1") (pin "3") (pinfunction "P$3_3") (pintype "bidirectional"))
    )
    (net (code "73") (name "SPI0_CE0_N") (class "Default")
      (node (ref "JP7") (pin "3") (pinfunction "3_3") (pintype "passive"))
      (node (ref "X1") (pin "24") (pinfunction "P$24_24") (pintype "bidirectional"))
    )
    (net (code "74") (name "SPI0_CE1_N") (class "Default")
      (node (ref "JP7") (pin "5") (pinfunction "5_5") (pintype "passive"))
      (node (ref "X1") (pin "26") (pinfunction "P$26_26") (pintype "bidirectional"))
    )
    (net (code "75") (name "SPI0_MISO") (class "Default")
      (node (ref "JP7") (pin "2") (pinfunction "2_2") (pintype "passive"))
      (node (ref "X1") (pin "21") (pinfunction "P$21_21") (pintype "bidirectional"))
    )
    (net (code "76") (name "SPI0_MOSI") (class "Default")
      (node (ref "JP7") (pin "1") (pinfunction "1_1") (pintype "passive"))
      (node (ref "X1") (pin "19") (pinfunction "P$19_19") (pintype "bidirectional"))
    )
    (net (code "77") (name "SPI0_SCLK") (class "Default")
      (node (ref "JP7") (pin "4") (pinfunction "4_4") (pintype "passive"))
      (node (ref "X1") (pin "23") (pinfunction "P$23_23") (pintype "bidirectional"))
    )
    (net (code "78") (name "SPI1_CS0") (class "Default")
      (node (ref "P9") (pin "28") (pinfunction "1_28") (pintype "passive"))
    )
    (net (code "79") (name "SPI1_CS1") (class "Default")
      (node (ref "P9") (pin "42") (pinfunction "1_42") (pintype "passive"))
      (node (ref "U5") (pin "5") (pinfunction "NSS_5") (pintype "input"))
    )
    (net (code "80") (name "SPI1_D0") (class "Default")
      (node (ref "P9") (pin "29") (pinfunction "1_29") (pintype "passive"))
      (node (ref "U5") (pin "2") (pinfunction "MISO_2") (pintype "input"))
    )
    (net (code "81") (name "SPI1_D1") (class "Default")
      (node (ref "P9") (pin "30") (pinfunction "1_30") (pintype "passive"))
      (node (ref "U5") (pin "3") (pinfunction "MOSI_3") (pintype "output"))
    )
    (net (code "82") (name "SPI1_SCLK") (class "Default")
      (node (ref "P9") (pin "31") (pinfunction "1_31") (pintype "passive"))
      (node (ref "U5") (pin "4") (pinfunction "SCK_4") (pintype "input"))
    )
    (net (code "83") (name "SW_5V_1") (class "Default")
      (node (ref "H1") (pin "2.13") (pinfunction "2.13_2.13") (pintype "bidirectional"))
      (node (ref "J13") (pin "1") (pinfunction "1_1") (pintype "bidirectional"))
    )
    (net (code "84") (name "SYS_RESET") (class "Default")
      (node (ref "P9") (pin "10") (pinfunction "1_10") (pintype "passive"))
    )
    (net (code "85") (name "TX+") (class "Default")
      (node (ref "J1") (pin "1") (pinfunction "1_1") (pintype "passive"))
      (node (ref "J2") (pin "4") (pinfunction "4_4") (pintype "passive"))
    )
    (net (code "86") (name "TX-") (class "Default")
      (node (ref "J1") (pin "2") (pinfunction "2_2") (pintype "passive"))
      (node (ref "J2") (pin "3") (pinfunction "3_3") (pintype "passive"))
    )
    (net (code "87") (name "UART1_RXD") (class "Default")
      (node (ref "J6") (pin "1") (pinfunction "1_1") (pintype "passive"))
      (node (ref "P9") (pin "26") (pinfunction "1_26") (pintype "passive"))
    )
    (net (code "88") (name "UART1_TXD") (class "Default")
      (node (ref "J6") (pin "2") (pinfunction "2_2") (pintype "passive"))
      (node (ref "P9") (pin "24") (pinfunction "1_24") (pintype "passive"))
    )
    (net (code "89") (name "UART2_RXD") (class "Default")
      (node (ref "P9") (pin "22") (pinfunction "1_22") (pintype "passive"))
      (node (ref "X1") (pin "8") (pinfunction "P$8_8") (pintype "bidirectional"))
    )
    (net (code "90") (name "UART2_TXD") (class "Default")
      (node (ref "P9") (pin "21") (pinfunction "1_21") (pintype "passive"))
      (node (ref "X1") (pin "10") (pinfunction "P$10_10") (pintype "bidirectional"))
    )
    (net (code "91") (name "UART4_CTSN") (class "Default")
      (node (ref "P8") (pin "35") (pinfunction "1_35") (pintype "passive"))
    )
    (net (code "92") (name "UART4_RTSN") (class "Default")
      (node (ref "P8") (pin "33") (pinfunction "1_33") (pintype "passive"))
    )
    (net (code "93") (name "UART5_RXD") (class "Default")
      (node (ref "P8") (pin "38") (pinfunction "1_38") (pintype "passive"))
      (node (ref "U6") (pin "44") (pinfunction "GPS_TXD0_44") (pintype "output"))
    )
    (net (code "94") (name "UART5_TXD") (class "Default")
      (node (ref "P8") (pin "37") (pinfunction "1_37") (pintype "passive"))
      (node (ref "U6") (pin "42") (pinfunction "GPS_RXDO_42") (pintype "input"))
    )
    (net (code "95") (name "unconnected-(H1-Pad1.7)") (class "Default")
      (node (ref "H1") (pin "1.7") (pinfunction "1.7_1.7") (pintype "bidirectional"))
    )
    (net (code "96") (name "unconnected-(H1-Pad1.8)") (class "Default")
      (node (ref "H1") (pin "1.8") (pinfunction "1.8_1.8") (pintype "bidirectional"))
    )
    (net (code "97") (name "unconnected-(H1-Pad1.9)") (class "Default")
      (node (ref "H1") (pin "1.9") (pinfunction "1.9_1.9") (pintype "bidirectional"))
    )
    (net (code "98") (name "unconnected-(H1-Pad1.10)") (class "Default")
      (node (ref "H1") (pin "1.10") (pinfunction "1.10_1.10") (pintype "bidirectional"))
    )
    (net (code "99") (name "unconnected-(H1-Pad1.11)") (class "Default")
      (node (ref "H1") (pin "1.11") (pinfunction "1.11_1.11") (pintype "bidirectional"))
    )
    (net (code "100") (name "unconnected-(H1-Pad1.12)") (class "Default")
      (node (ref "H1") (pin "1.12") (pinfunction "1.12_1.12") (pintype "bidirectional"))
    )
    (net (code "101") (name "unconnected-(H1-Pad1.13)") (class "Default")
      (node (ref "H1") (pin "1.13") (pinfunction "1.13_1.13") (pintype "bidirectional"))
    )
    (net (code "102") (name "unconnected-(H1-Pad1.14)") (class "Default")
      (node (ref "H1") (pin "1.14") (pinfunction "1.14_1.14") (pintype "bidirectional"))
    )
    (net (code "103") (name "unconnected-(H1-Pad1.15)") (class "Default")
      (node (ref "H1") (pin "1.15") (pinfunction "1.15_1.15") (pintype "bidirectional"))
    )
    (net (code "104") (name "unconnected-(H1-Pad1.16)") (class "Default")
      (node (ref "H1") (pin "1.16") (pinfunction "1.16_1.16") (pintype "bidirectional"))
    )
    (net (code "105") (name "unconnected-(H1-Pad1.17)") (class "Default")
      (node (ref "H1") (pin "1.17") (pinfunction "1.17_1.17") (pintype "bidirectional"))
    )
    (net (code "106") (name "unconnected-(H1-Pad1.18)") (class "Default")
      (node (ref "H1") (pin "1.18") (pinfunction "1.18_1.18") (pintype "bidirectional"))
    )
    (net (code "107") (name "unconnected-(H1-Pad1.19)") (class "Default")
      (node (ref "H1") (pin "1.19") (pinfunction "1.19_1.19") (pintype "bidirectional"))
    )
    (net (code "108") (name "unconnected-(H1-Pad1.20)") (class "Default")
      (node (ref "H1") (pin "1.20") (pinfunction "1.20_1.20") (pintype "bidirectional"))
    )
    (net (code "109") (name "unconnected-(H1-Pad1.21)") (class "Default")
      (node (ref "H1") (pin "1.21") (pinfunction "1.21_1.21") (pintype "bidirectional"))
    )
    (net (code "110") (name "unconnected-(H1-Pad1.22)") (class "Default")
      (node (ref "H1") (pin "1.22") (pinfunction "1.22_1.22") (pintype "bidirectional"))
    )
    (net (code "111") (name "unconnected-(H1-Pad1.23)") (class "Default")
      (node (ref "H1") (pin "1.23") (pinfunction "1.23_1.23") (pintype "bidirectional"))
    )
    (net (code "112") (name "unconnected-(H1-Pad1.24)") (class "Default")
      (node (ref "H1") (pin "1.24") (pinfunction "1.24_1.24") (pintype "bidirectional"))
    )
    (net (code "113") (name "unconnected-(H1-Pad1.25)") (class "Default")
      (node (ref "H1") (pin "1.25") (pinfunction "1.25_1.25") (pintype "bidirectional"))
    )
    (net (code "114") (name "unconnected-(H1-Pad1.26)") (class "Default")
      (node (ref "H1") (pin "1.26") (pinfunction "1.26_1.26") (pintype "bidirectional"))
    )
    (net (code "115") (name "unconnected-(H1-Pad1.27)") (class "Default")
      (node (ref "H1") (pin "1.27") (pinfunction "1.27_1.27") (pintype "bidirectional"))
    )
    (net (code "116") (name "unconnected-(H1-Pad1.28)") (class "Default")
      (node (ref "H1") (pin "1.28") (pinfunction "1.28_1.28") (pintype "bidirectional"))
    )
    (net (code "117") (name "unconnected-(H1-Pad1.29)") (class "Default")
      (node (ref "H1") (pin "1.29") (pinfunction "1.29_1.29") (pintype "bidirectional"))
    )
    (net (code "118") (name "unconnected-(H1-Pad1.30)") (class "Default")
      (node (ref "H1") (pin "1.30") (pinfunction "1.30_1.30") (pintype "bidirectional"))
    )
    (net (code "119") (name "unconnected-(H1-Pad1.31)") (class "Default")
      (node (ref "H1") (pin "1.31") (pinfunction "1.31_1.31") (pintype "bidirectional"))
    )
    (net (code "120") (name "unconnected-(H1-Pad1.32)") (class "Default")
      (node (ref "H1") (pin "1.32") (pinfunction "1.32_1.32") (pintype "bidirectional"))
    )
    (net (code "121") (name "unconnected-(H1-Pad1.33)") (class "Default")
      (node (ref "H1") (pin "1.33") (pinfunction "1.33_1.33") (pintype "bidirectional"))
    )
    (net (code "122") (name "unconnected-(H1-Pad1.34)") (class "Default")
      (node (ref "H1") (pin "1.34") (pinfunction "1.34_1.34") (pintype "bidirectional"))
    )
    (net (code "123") (name "unconnected-(H1-Pad1.35)") (class "Default")
      (node (ref "H1") (pin "1.35") (pinfunction "1.35_1.35") (pintype "bidirectional"))
    )
    (net (code "124") (name "unconnected-(H1-Pad1.36)") (class "Default")
      (node (ref "H1") (pin "1.36") (pinfunction "1.36_1.36") (pintype "bidirectional"))
    )
    (net (code "125") (name "unconnected-(H1-Pad1.37)") (class "Default")
      (node (ref "H1") (pin "1.37") (pinfunction "1.37_1.37") (pintype "bidirectional"))
    )
    (net (code "126") (name "unconnected-(H1-Pad1.38)") (class "Default")
      (node (ref "H1") (pin "1.38") (pinfunction "1.38_1.38") (pintype "bidirectional"))
    )
    (net (code "127") (name "unconnected-(H1-Pad1.39)") (class "Default")
      (node (ref "H1") (pin "1.39") (pinfunction "1.39_1.39") (pintype "bidirectional"))
    )
    (net (code "128") (name "unconnected-(H1-Pad1.40)") (class "Default")
      (node (ref "H1") (pin "1.40") (pinfunction "1.40_1.40") (pintype "bidirectional"))
    )
    (net (code "129") (name "unconnected-(H1-Pad1.41)") (class "Default")
      (node (ref "H1") (pin "1.41") (pinfunction "1.41_1.41") (pintype "bidirectional"))
    )
    (net (code "130") (name "unconnected-(H1-Pad1.42)") (class "Default")
      (node (ref "H1") (pin "1.42") (pinfunction "1.42_1.42") (pintype "bidirectional"))
    )
    (net (code "131") (name "unconnected-(H1-Pad1.43)") (class "Default")
      (node (ref "H1") (pin "1.43") (pinfunction "1.43_1.43") (pintype "bidirectional"))
    )
    (net (code "132") (name "unconnected-(H1-Pad1.44)") (class "Default")
      (node (ref "H1") (pin "1.44") (pinfunction "1.44_1.44") (pintype "bidirectional"))
    )
    (net (code "133") (name "unconnected-(H1-Pad1.45)") (class "Default")
      (node (ref "H1") (pin "1.45") (pinfunction "1.45_1.45") (pintype "bidirectional"))
    )
    (net (code "134") (name "unconnected-(H1-Pad1.46)") (class "Default")
      (node (ref "H1") (pin "1.46") (pinfunction "1.46_1.46") (pintype "bidirectional"))
    )
    (net (code "135") (name "unconnected-(H1-Pad1.47)") (class "Default")
      (node (ref "H1") (pin "1.47") (pinfunction "1.47_1.47") (pintype "bidirectional"))
    )
    (net (code "136") (name "unconnected-(H1-Pad1.48)") (class "Default")
      (node (ref "H1") (pin "1.48") (pinfunction "1.48_1.48") (pintype "bidirectional"))
    )
    (net (code "137") (name "unconnected-(H1-Pad1.49)") (class "Default")
      (node (ref "H1") (pin "1.49") (pinfunction "1.49_1.49") (pintype "bidirectional"))
    )
    (net (code "138") (name "unconnected-(H1-Pad1.50)") (class "Default")
      (node (ref "H1") (pin "1.50") (pinfunction "1.50_1.50") (pintype "bidirectional"))
    )
    (net (code "139") (name "unconnected-(H1-Pad1.51)") (class "Default")
      (node (ref "H1") (pin "1.51") (pinfunction "1.51_1.51") (pintype "bidirectional"))
    )
    (net (code "140") (name "unconnected-(H1-Pad1.52)") (class "Default")
      (node (ref "H1") (pin "1.52") (pinfunction "1.52_1.52") (pintype "bidirectional"))
    )
    (net (code "141") (name "unconnected-(H1-Pad2.1)") (class "Default")
      (node (ref "H1") (pin "2.1") (pinfunction "2.1_2.1") (pintype "bidirectional"))
    )
    (net (code "142") (name "unconnected-(H1-Pad2.2)") (class "Default")
      (node (ref "H1") (pin "2.2") (pinfunction "2.2_2.2") (pintype "bidirectional"))
    )
    (net (code "143") (name "unconnected-(H1-Pad2.3)") (class "Default")
      (node (ref "H1") (pin "2.3") (pinfunction "2.3_2.3") (pintype "bidirectional"))
    )
    (net (code "144") (name "unconnected-(H1-Pad2.4)") (class "Default")
      (node (ref "H1") (pin "2.4") (pinfunction "2.4_2.4") (pintype "bidirectional"))
    )
    (net (code "145") (name "unconnected-(H1-Pad2.5)") (class "Default")
      (node (ref "H1") (pin "2.5") (pinfunction "2.5_2.5") (pintype "bidirectional"))
    )
    (net (code "146") (name "unconnected-(H1-Pad2.6)") (class "Default")
      (node (ref "H1") (pin "2.6") (pinfunction "2.6_2.6") (pintype "bidirectional"))
    )
    (net (code "147") (name "unconnected-(H1-Pad2.8)") (class "Default")
      (node (ref "H1") (pin "2.8") (pinfunction "2.8_2.8") (pintype "bidirectional"))
    )
    (net (code "148") (name "unconnected-(H1-Pad2.9)") (class "Default")
      (node (ref "H1") (pin "2.9") (pinfunction "2.9_2.9") (pintype "bidirectional"))
    )
    (net (code "149") (name "unconnected-(H1-Pad2.10)") (class "Default")
      (node (ref "H1") (pin "2.10") (pinfunction "2.10_2.10") (pintype "bidirectional"))
    )
    (net (code "150") (name "unconnected-(H1-Pad2.11)") (class "Default")
      (node (ref "H1") (pin "2.11") (pinfunction "2.11_2.11") (pintype "bidirectional"))
    )
    (net (code "151") (name "unconnected-(H1-Pad2.12)") (class "Default")
      (node (ref "H1") (pin "2.12") (pinfunction "2.12_2.12") (pintype "bidirectional"))
    )
    (net (code "152") (name "unconnected-(H1-Pad2.15)") (class "Default")
      (node (ref "H1") (pin "2.15") (pinfunction "2.15_2.15") (pintype "bidirectional"))
    )
    (net (code "153") (name "unconnected-(H1-Pad2.16)") (class "Default")
      (node (ref "H1") (pin "2.16") (pinfunction "2.16_2.16") (pintype "bidirectional"))
    )
    (net (code "154") (name "unconnected-(H1-Pad2.18)") (class "Default")
      (node (ref "H1") (pin "2.18") (pinfunction "2.18_2.18") (pintype "bidirectional"))
    )
    (net (code "155") (name "unconnected-(H1-Pad2.19)") (class "Default")
      (node (ref "H1") (pin "2.19") (pinfunction "2.19_2.19") (pintype "bidirectional"))
    )
    (net (code "156") (name "unconnected-(H1-Pad2.20)") (class "Default")
      (node (ref "H1") (pin "2.20") (pinfunction "2.20_2.20") (pintype "bidirectional"))
    )
    (net (code "157") (name "unconnected-(H1-Pad2.23)") (class "Default")
      (node (ref "H1") (pin "2.23") (pinfunction "2.23_2.23") (pintype "bidirectional"))
    )
    (net (code "158") (name "unconnected-(H1-Pad2.24)") (class "Default")
      (node (ref "H1") (pin "2.24") (pinfunction "2.24_2.24") (pintype "bidirectional"))
    )
    (net (code "159") (name "unconnected-(H1-Pad2.31)") (class "Default")
      (node (ref "H1") (pin "2.31") (pinfunction "2.31_2.31") (pintype "bidirectional"))
    )
    (net (code "160") (name "unconnected-(H1-Pad2.33)") (class "Default")
      (node (ref "H1") (pin "2.33") (pinfunction "2.33_2.33") (pintype "bidirectional"))
    )
    (net (code "161") (name "unconnected-(H1-Pad2.34)") (class "Default")
      (node (ref "H1") (pin "2.34") (pinfunction "2.34_2.34") (pintype "bidirectional"))
    )
    (net (code "162") (name "unconnected-(H1-Pad2.35)") (class "Default")
      (node (ref "H1") (pin "2.35") (pinfunction "2.35_2.35") (pintype "bidirectional"))
    )
    (net (code "163") (name "unconnected-(H1-Pad2.36)") (class "Default")
      (node (ref "H1") (pin "2.36") (pinfunction "2.36_2.36") (pintype "bidirectional"))
    )
    (net (code "164") (name "unconnected-(H1-Pad2.37)") (class "Default")
      (node (ref "H1") (pin "2.37") (pinfunction "2.37_2.37") (pintype "bidirectional"))
    )
    (net (code "165") (name "unconnected-(H1-Pad2.38)") (class "Default")
      (node (ref "H1") (pin "2.38") (pinfunction "2.38_2.38") (pintype "bidirectional"))
    )
    (net (code "166") (name "unconnected-(H1-Pad2.39)") (class "Default")
      (node (ref "H1") (pin "2.39") (pinfunction "2.39_2.39") (pintype "bidirectional"))
    )
    (net (code "167") (name "unconnected-(H1-Pad2.40)") (class "Default")
      (node (ref "H1") (pin "2.40") (pinfunction "2.40_2.40") (pintype "bidirectional"))
    )
    (net (code "168") (name "unconnected-(H1-Pad2.41)") (class "Default")
      (node (ref "H1") (pin "2.41") (pinfunction "2.41_2.41") (pintype "bidirectional"))
    )
    (net (code "169") (name "unconnected-(H1-Pad2.42)") (class "Default")
      (node (ref "H1") (pin "2.42") (pinfunction "2.42_2.42") (pintype "bidirectional"))
    )
    (net (code "170") (name "unconnected-(H1-Pad2.43)") (class "Default")
      (node (ref "H1") (pin "2.43") (pinfunction "2.43_2.43") (pintype "bidirectional"))
    )
    (net (code "171") (name "unconnected-(H1-Pad2.44)") (class "Default")
      (node (ref "H1") (pin "2.44") (pinfunction "2.44_2.44") (pintype "bidirectional"))
    )
    (net (code "172") (name "unconnected-(H1-Pad2.45)") (class "Default")
      (node (ref "H1") (pin "2.45") (pinfunction "2.45_2.45") (pintype "bidirectional"))
    )
    (net (code "173") (name "unconnected-(H1-Pad2.46)") (class "Default")
      (node (ref "H1") (pin "2.46") (pinfunction "2.46_2.46") (pintype "bidirectional"))
    )
    (net (code "174") (name "unconnected-(H1-Pad2.49)") (class "Default")
      (node (ref "H1") (pin "2.49") (pinfunction "2.49_2.49") (pintype "bidirectional"))
    )
    (net (code "175") (name "unconnected-(H1-Pad2.50)") (class "Default")
      (node (ref "H1") (pin "2.50") (pinfunction "2.50_2.50") (pintype "bidirectional"))
    )
    (net (code "176") (name "unconnected-(H1-Pad2.51)") (class "Default")
      (node (ref "H1") (pin "2.51") (pinfunction "2.51_2.51") (pintype "bidirectional"))
    )
    (net (code "177") (name "unconnected-(H1-Pad2.52)") (class "Default")
      (node (ref "H1") (pin "2.52") (pinfunction "2.52_2.52") (pintype "bidirectional"))
    )
    (net (code "178") (name "unconnected-(H1-PadP$1)") (class "Default")
      (node (ref "H1") (pin "P$1") (pinfunction "P$1_P$1") (pintype "bidirectional"))
    )
    (net (code "179") (name "unconnected-(H1-PadP$2)") (class "Default")
      (node (ref "H1") (pin "P$2") (pinfunction "P$2_P$2") (pintype "bidirectional"))
    )
    (net (code "180") (name "unconnected-(H1-PadP$3)") (class "Default")
      (node (ref "H1") (pin "P$3") (pinfunction "P$3_P$3") (pintype "bidirectional"))
    )
    (net (code "181") (name "unconnected-(JP4-Pad1)") (class "Default")
      (node (ref "JP4") (pin "1") (pinfunction "1_1") (pintype "passive"))
    )
    (net (code "182") (name "unconnected-(P8AB-1-Pad34)") (class "Default")
      (node (ref "P8") (pin "34") (pinfunction "1_34") (pintype "passive"))
    )
    (net (code "183") (name "unconnected-(P8AS-1-Pad8)") (class "Default")
      (node (ref "P8") (pin "8") (pinfunction "1_8") (pintype "passive"))
    )
    (net (code "184") (name "unconnected-(P8AT-1-Pad9)") (class "Default")
      (node (ref "P8") (pin "9") (pinfunction "1_9") (pintype "passive"))
    )
    (net (code "185") (name "unconnected-(P8B-1-Pad10)") (class "Default")
      (node (ref "P8") (pin "10") (pinfunction "1_10") (pintype "passive"))
    )
    (net (code "186") (name "unconnected-(P8E-1-Pad13)") (class "Default")
      (node (ref "P8") (pin "13") (pinfunction "1_13") (pintype "passive"))
    )
    (net (code "187") (name "unconnected-(P8F-1-Pad14)") (class "Default")
      (node (ref "P8") (pin "14") (pinfunction "1_14") (pintype "passive"))
    )
    (net (code "188") (name "unconnected-(P8K-1-Pad19)") (class "Default")
      (node (ref "P8") (pin "19") (pinfunction "1_19") (pintype "passive"))
    )
    (net (code "189") (name "unconnected-(P8O-1-Pad22)") (class "Default")
      (node (ref "P8") (pin "22") (pinfunction "1_22") (pintype "passive"))
    )
    (net (code "190") (name "unconnected-(P9AJ-1-Pad41)") (class "Default")
      (node (ref "P9") (pin "41") (pinfunction "1_41") (pintype "passive"))
    )
    (net (code "191") (name "unconnected-(P9AL-1-Pad43)") (class "Default")
      (node (ref "P9") (pin "43") (pinfunction "1_43") (pintype "passive"))
    )
    (net (code "192") (name "unconnected-(P9AM-1-Pad44)") (class "Default")
      (node (ref "P9") (pin "44") (pinfunction "1_44") (pintype "passive"))
    )
    (net (code "193") (name "unconnected-(P9AN-1-Pad45)") (class "Default")
      (node (ref "P9") (pin "45") (pinfunction "1_45") (pintype "passive"))
    )
    (net (code "194") (name "unconnected-(P9AO-1-Pad46)") (class "Default")
      (node (ref "P9") (pin "46") (pinfunction "1_46") (pintype "passive"))
    )
    (net (code "195") (name "unconnected-(P9AR-1-Pad7)") (class "Default")
      (node (ref "P9") (pin "7") (pinfunction "1_7") (pintype "passive"))
    )
    (net (code "196") (name "unconnected-(P9AS-1-Pad8)") (class "Default")
      (node (ref "P9") (pin "8") (pinfunction "1_8") (pintype "passive"))
    )
    (net (code "197") (name "unconnected-(P9AT-1-Pad9)") (class "Default")
      (node (ref "P9") (pin "9") (pinfunction "1_9") (pintype "passive"))
    )
    (net (code "198") (name "unconnected-(P9F-1-Pad14)") (class "Default")
      (node (ref "P9") (pin "14") (pinfunction "1_14") (pintype "passive"))
    )
    (net (code "199") (name "unconnected-(P9H-1-Pad16)") (class "Default")
      (node (ref "P9") (pin "16") (pinfunction "1_16") (pintype "passive"))
    )
    (net (code "200") (name "unconnected-(P9I-1-Pad17)") (class "Default")
      (node (ref "P9") (pin "17") (pinfunction "1_17") (pintype "passive"))
    )
    (net (code "201") (name "unconnected-(P9J-1-Pad18)") (class "Default")
      (node (ref "P9") (pin "18") (pinfunction "1_18") (pintype "passive"))
    )
    (net (code "202") (name "unconnected-(P9Z-1-Pad32)") (class "Default")
      (node (ref "P9") (pin "32") (pinfunction "1_32") (pintype "passive"))
    )
    (net (code "203") (name "unconnected-(U1-NC-Pad7)") (class "Default")
      (node (ref "U1") (pin "7") (pinfunction "NC_7") (pintype "no_connect"))
    )
    (net (code "204") (name "unconnected-(U1-NC_2-Pad2)") (class "Default")
      (node (ref "U1") (pin "2") (pinfunction "NC_2_2") (pintype "no_connect"))
    )
    (net (code "205") (name "unconnected-(U1-NC_3-Pad3)") (class "Default")
      (node (ref "U1") (pin "3") (pinfunction "NC_3_3") (pintype "no_connect"))
    )
    (net (code "206") (name "unconnected-(U1-NC_4-Pad6)") (class "Default")
      (node (ref "U1") (pin "6") (pinfunction "NC_4_6") (pintype "no_connect"))
    )
    (net (code "207") (name "unconnected-(U5-DIO0-Pad14)") (class "Default")
      (node (ref "U5") (pin "14") (pinfunction "DIO0_14") (pintype "bidirectional"))
    )
    (net (code "208") (name "unconnected-(U5-DIO1-Pad15)") (class "Default")
      (node (ref "U5") (pin "15") (pinfunction "DIO1_15") (pintype "bidirectional"))
    )
    (net (code "209") (name "unconnected-(U5-DIO2-Pad16)") (class "Default")
      (node (ref "U5") (pin "16") (pinfunction "DIO2_16") (pintype "bidirectional"))
    )
    (net (code "210") (name "unconnected-(U5-DIO3-Pad11)") (class "Default")
      (node (ref "U5") (pin "11") (pinfunction "DIO3_11") (pintype "bidirectional"))
    )
    (net (code "211") (name "unconnected-(U5-DIO4-Pad12)") (class "Default")
      (node (ref "U5") (pin "12") (pinfunction "DIO4_12") (pintype "bidirectional"))
    )
    (net (code "212") (name "unconnected-(U5-DIO5-Pad7)") (class "Default")
      (node (ref "U5") (pin "7") (pinfunction "DIO5_7") (pintype "bidirectional"))
    )
    (net (code "213") (name "unconnected-(U6-P$3-Pad3)") (class "Default")
      (node (ref "U6") (pin "3") (pinfunction "P$3_3") (pintype "bidirectional"))
    )
    (net (code "214") (name "unconnected-(U6-P$4-Pad4)") (class "Default")
      (node (ref "U6") (pin "4") (pinfunction "P$4_4") (pintype "bidirectional"))
    )
    (net (code "215") (name "unconnected-(U6-P$5-Pad5)") (class "Default")
      (node (ref "U6") (pin "5") (pinfunction "P$5_5") (pintype "bidirectional"))
    )
    (net (code "216") (name "unconnected-(U6-P$6-Pad6)") (class "Default")
      (node (ref "U6") (pin "6") (pinfunction "P$6_6") (pintype "bidirectional"))
    )
    (net (code "217") (name "unconnected-(U6-P$8-Pad8)") (class "Default")
      (node (ref "U6") (pin "8") (pinfunction "P$8_8") (pintype "bidirectional"))
    )
    (net (code "218") (name "unconnected-(U6-P$10-Pad10)") (class "Default")
      (node (ref "U6") (pin "10") (pinfunction "P$10_10") (pintype "bidirectional"))
    )
    (net (code "219") (name "unconnected-(U6-P$12-Pad12)") (class "Default")
      (node (ref "U6") (pin "12") (pinfunction "P$12_12") (pintype "bidirectional"))
    )
    (net (code "220") (name "unconnected-(U6-P$13-Pad13)") (class "Default")
      (node (ref "U6") (pin "13") (pinfunction "P$13_13") (pintype "bidirectional"))
    )
    (net (code "221") (name "unconnected-(U6-P$14-Pad14)") (class "Default")
      (node (ref "U6") (pin "14") (pinfunction "P$14_14") (pintype "bidirectional"))
    )
    (net (code "222") (name "unconnected-(U6-P$15-Pad15)") (class "Default")
      (node (ref "U6") (pin "15") (pinfunction "P$15_15") (pintype "bidirectional"))
    )
    (net (code "223") (name "unconnected-(U6-P$16-Pad16)") (class "Default")
      (node (ref "U6") (pin "16") (pinfunction "P$16_16") (pintype "bidirectional"))
    )
    (net (code "224") (name "unconnected-(U6-P$17-Pad17)") (class "Default")
      (node (ref "U6") (pin "17") (pinfunction "P$17_17") (pintype "bidirectional"))
    )
    (net (code "225") (name "unconnected-(U6-P$19-Pad19)") (class "Default")
      (node (ref "U6") (pin "19") (pinfunction "P$19_19") (pintype "bidirectional"))
    )
    (net (code "226") (name "unconnected-(U6-P$20-Pad20)") (class "Default")
      (node (ref "U6") (pin "20") (pinfunction "P$20_20") (pintype "bidirectional"))
    )
    (net (code "227") (name "unconnected-(U6-P$22-Pad22)") (class "Default")
      (node (ref "U6") (pin "22") (pinfunction "P$22_22") (pintype "bidirectional"))
    )
    (net (code "228") (name "unconnected-(U6-P$23-Pad23)") (class "Default")
      (node (ref "U6") (pin "23") (pinfunction "P$23_23") (pintype "bidirectional"))
    )
    (net (code "229") (name "unconnected-(U6-P$24-Pad24)") (class "Default")
      (node (ref "U6") (pin "24") (pinfunction "P$24_24") (pintype "bidirectional"))
    )
    (net (code "230") (name "unconnected-(U6-P$25-Pad25)") (class "Default")
      (node (ref "U6") (pin "25") (pinfunction "P$25_25") (pintype "bidirectional"))
    )
    (net (code "231") (name "unconnected-(U6-P$26-Pad26)") (class "Default")
      (node (ref "U6") (pin "26") (pinfunction "P$26_26") (pintype "bidirectional"))
    )
    (net (code "232") (name "unconnected-(U6-P$27-Pad27)") (class "Default")
      (node (ref "U6") (pin "27") (pinfunction "P$27_27") (pintype "bidirectional"))
    )
    (net (code "233") (name "unconnected-(U6-P$28-Pad28)") (class "Default")
      (node (ref "U6") (pin "28") (pinfunction "P$28_28") (pintype "bidirectional"))
    )
    (net (code "234") (name "unconnected-(U6-P$29-Pad29)") (class "Default")
      (node (ref "U6") (pin "29") (pinfunction "P$29_29") (pintype "bidirectional"))
    )
    (net (code "235") (name "unconnected-(U6-P$30-Pad30)") (class "Default")
      (node (ref "U6") (pin "30") (pinfunction "P$30_30") (pintype "bidirectional"))
    )
    (net (code "236") (name "unconnected-(U6-P$31-Pad31)") (class "Default")
      (node (ref "U6") (pin "31") (pinfunction "P$31_31") (pintype "bidirectional"))
    )
    (net (code "237") (name "unconnected-(U6-P$33-Pad33)") (class "Default")
      (node (ref "U6") (pin "33") (pinfunction "P$33_33") (pintype "bidirectional"))
    )
    (net (code "238") (name "unconnected-(U6-P$34-Pad34)") (class "Default")
      (node (ref "U6") (pin "34") (pinfunction "P$34_34") (pintype "bidirectional"))
    )
    (net (code "239") (name "unconnected-(U6-P$35-Pad35)") (class "Default")
      (node (ref "U6") (pin "35") (pinfunction "P$35_35") (pintype "bidirectional"))
    )
    (net (code "240") (name "unconnected-(U6-P$36-Pad36)") (class "Default")
      (node (ref "U6") (pin "36") (pinfunction "P$36_36") (pintype "bidirectional"))
    )
    (net (code "241") (name "unconnected-(U6-P$37-Pad37)") (class "Default")
      (node (ref "U6") (pin "37") (pinfunction "P$37_37") (pintype "bidirectional"))
    )
    (net (code "242") (name "unconnected-(U6-P$38-Pad38)") (class "Default")
      (node (ref "U6") (pin "38") (pinfunction "P$38_38") (pintype "bidirectional"))
    )
    (net (code "243") (name "unconnected-(U6-P$39-Pad39)") (class "Default")
      (node (ref "U6") (pin "39") (pinfunction "P$39_39") (pintype "bidirectional"))
    )
    (net (code "244") (name "unconnected-(U6-P$40-Pad40)") (class "Default")
      (node (ref "U6") (pin "40") (pinfunction "P$40_40") (pintype "bidirectional"))
    )
    (net (code "245") (name "unconnected-(U6-P$41-Pad41)") (class "Default")
      (node (ref "U6") (pin "41") (pinfunction "P$41_41") (pintype "bidirectional"))
    )
    (net (code "246") (name "unconnected-(U6-P$43-Pad43)") (class "Default")
      (node (ref "U6") (pin "43") (pinfunction "P$43_43") (pintype "bidirectional"))
    )
    (net (code "247") (name "unconnected-(U6-P$45-Pad45)") (class "Default")
      (node (ref "U6") (pin "45") (pinfunction "P$45_45") (pintype "bidirectional"))
    )
    (net (code "248") (name "unconnected-(U6-P$46-Pad46)") (class "Default")
      (node (ref "U6") (pin "46") (pinfunction "P$46_46") (pintype "bidirectional"))
    )
    (net (code "249") (name "unconnected-(U6-P$47-Pad47)") (class "Default")
      (node (ref "U6") (pin "47") (pinfunction "P$47_47") (pintype "bidirectional"))
    )
    (net (code "250") (name "unconnected-(U6-P$48-Pad48)") (class "Default")
      (node (ref "U6") (pin "48") (pinfunction "P$48_48") (pintype "bidirectional"))
    )
    (net (code "251") (name "unconnected-(U6-P$49-Pad49)") (class "Default")
      (node (ref "U6") (pin "49") (pinfunction "P$49_49") (pintype "bidirectional"))
    )
    (net (code "252") (name "unconnected-(U6-P$50-Pad50)") (class "Default")
      (node (ref "U6") (pin "50") (pinfunction "P$50_50") (pintype "bidirectional"))
    )
    (net (code "253") (name "unconnected-(U6-P$51-Pad51)") (class "Default")
      (node (ref "U6") (pin "51") (pinfunction "P$51_51") (pintype "bidirectional"))
    )
    (net (code "254") (name "unconnected-(U6-P$52-Pad52)") (class "Default")
      (node (ref "U6") (pin "52") (pinfunction "P$52_52") (pintype "bidirectional"))
    )
    (net (code "255") (name "unconnected-(U6-P$53-Pad53)") (class "Default")
      (node (ref "U6") (pin "53") (pinfunction "P$53_53") (pintype "bidirectional"))
    )
    (net (code "256") (name "unconnected-(U6-P$54-Pad54)") (class "Default")
      (node (ref "U6") (pin "54") (pinfunction "P$54_54") (pintype "bidirectional"))
    )
    (net (code "257") (name "unconnected-(U6-P$55-Pad55)") (class "Default")
      (node (ref "U6") (pin "55") (pinfunction "P$55_55") (pintype "bidirectional"))
    )
    (net (code "258") (name "unconnected-(U6-P$56-Pad56)") (class "Default")
      (node (ref "U6") (pin "56") (pinfunction "P$56_56") (pintype "bidirectional"))
    )
    (net (code "259") (name "unconnected-(U6-P$57-Pad57)") (class "Default")
      (node (ref "U6") (pin "57") (pinfunction "P$57_57") (pintype "bidirectional"))
    )
    (net (code "260") (name "unconnected-(U6-P$58-Pad58)") (class "Default")
      (node (ref "U6") (pin "58") (pinfunction "P$58_58") (pintype "bidirectional"))
    )
    (net (code "261") (name "unconnected-(U6-P$59-Pad59)") (class "Default")
      (node (ref "U6") (pin "59") (pinfunction "P$59_59") (pintype "bidirectional"))
    )
    (net (code "262") (name "unconnected-(U6-P$60-Pad60)") (class "Default")
      (node (ref "U6") (pin "60") (pinfunction "P$60_60") (pintype "bidirectional"))
    )
    (net (code "263") (name "unconnected-(U6-P$61-Pad61)") (class "Default")
      (node (ref "U6") (pin "61") (pinfunction "P$61_61") (pintype "bidirectional"))
    )
    (net (code "264") (name "unconnected-(U6-P$62-Pad62)") (class "Default")
      (node (ref "U6") (pin "62") (pinfunction "P$62_62") (pintype "bidirectional"))
    )
    (net (code "265") (name "unconnected-(U6-P$63-Pad63)") (class "Default")
      (node (ref "U6") (pin "63") (pinfunction "P$63_63") (pintype "bidirectional"))
    )
    (net (code "266") (name "unconnected-(U6-P$65-Pad65)") (class "Default")
      (node (ref "U6") (pin "65") (pinfunction "P$65_65") (pintype "bidirectional"))
    )
    (net (code "267") (name "unconnected-(U6-P$66-Pad66)") (class "Default")
      (node (ref "U6") (pin "66") (pinfunction "P$66_66") (pintype "bidirectional"))
    )
    (net (code "268") (name "unconnected-(U6-P$67-Pad67)") (class "Default")
      (node (ref "U6") (pin "67") (pinfunction "P$67_67") (pintype "bidirectional"))
    )
    (net (code "269") (name "unconnected-(U6-P$68-Pad68)") (class "Default")
      (node (ref "U6") (pin "68") (pinfunction "P$68_68") (pintype "bidirectional"))
    )
    (net (code "270") (name "unconnected-(U6-P$69-Pad69)") (class "Default")
      (node (ref "U6") (pin "69") (pinfunction "P$69_69") (pintype "bidirectional"))
    )
    (net (code "271") (name "unconnected-(X1-P$1-Pad1)") (class "Default")
      (node (ref "X1") (pin "1") (pinfunction "P$1_1") (pintype "bidirectional"))
    )
    (net (code "272") (name "unconnected-(X1-P$4-Pad4)") (class "Default")
      (node (ref "X1") (pin "4") (pinfunction "P$4_4") (pintype "bidirectional"))
    )
    (net (code "273") (name "unconnected-(X1-P$6-Pad6)") (class "Default")
      (node (ref "X1") (pin "6") (pinfunction "P$6_6") (pintype "bidirectional"))
    )
    (net (code "274") (name "unconnected-(X1-P$7-Pad7)") (class "Default")
      (node (ref "X1") (pin "7") (pinfunction "P$7_7") (pintype "bidirectional"))
    )
    (net (code "275") (name "unconnected-(X1-P$9-Pad9)") (class "Default")
      (node (ref "X1") (pin "9") (pinfunction "P$9_9") (pintype "bidirectional"))
    )
    (net (code "276") (name "unconnected-(X1-P$12-Pad12)") (class "Default")
      (node (ref "X1") (pin "12") (pinfunction "P$12_12") (pintype "bidirectional"))
    )
    (net (code "277") (name "unconnected-(X1-P$14-Pad14)") (class "Default")
      (node (ref "X1") (pin "14") (pinfunction "P$14_14") (pintype "bidirectional"))
    )
    (net (code "278") (name "unconnected-(X1-P$17-Pad17)") (class "Default")
      (node (ref "X1") (pin "17") (pinfunction "P$17_17") (pintype "bidirectional"))
    )
    (net (code "279") (name "unconnected-(X1-P$20-Pad20)") (class "Default")
      (node (ref "X1") (pin "20") (pinfunction "P$20_20") (pintype "bidirectional"))
    )
    (net (code "280") (name "unconnected-(X1-P$25-Pad25)") (class "Default")
      (node (ref "X1") (pin "25") (pinfunction "P$25_25") (pintype "bidirectional"))
    )
    (net (code "281") (name "unconnected-(X1-P$27-Pad27)") (class "Default")
      (node (ref "X1") (pin "27") (pinfunction "P$27_27") (pintype "bidirectional"))
    )
    (net (code "282") (name "unconnected-(X1-P$28-Pad28)") (class "Default")
      (node (ref "X1") (pin "28") (pinfunction "P$28_28") (pintype "bidirectional"))
    )
    (net (code "283") (name "unconnected-(X1-P$29-Pad29)") (class "Default")
      (node (ref "X1") (pin "29") (pinfunction "P$29_29") (pintype "bidirectional"))
    )
    (net (code "284") (name "unconnected-(X1-P$30-Pad30)") (class "Default")
      (node (ref "X1") (pin "30") (pinfunction "P$30_30") (pintype "bidirectional"))
    )
    (net (code "285") (name "unconnected-(X1-P$31-Pad31)") (class "Default")
      (node (ref "X1") (pin "31") (pinfunction "P$31_31") (pintype "bidirectional"))
    )
    (net (code "286") (name "unconnected-(X1-P$32-Pad32)") (class "Default")
      (node (ref "X1") (pin "32") (pinfunction "P$32_32") (pintype "bidirectional"))
    )
    (net (code "287") (name "unconnected-(X1-P$33-Pad33)") (class "Default")
      (node (ref "X1") (pin "33") (pinfunction "P$33_33") (pintype "bidirectional"))
    )
    (net (code "288") (name "unconnected-(X1-P$34-Pad34)") (class "Default")
      (node (ref "X1") (pin "34") (pinfunction "P$34_34") (pintype "bidirectional"))
    )
    (net (code "289") (name "unconnected-(X1-P$35-Pad35)") (class "Default")
      (node (ref "X1") (pin "35") (pinfunction "P$35_35") (pintype "bidirectional"))
    )
    (net (code "290") (name "unconnected-(X1-P$36-Pad36)") (class "Default")
      (node (ref "X1") (pin "36") (pinfunction "P$36_36") (pintype "bidirectional"))
    )
    (net (code "291") (name "unconnected-(X1-P$37-Pad37)") (class "Default")
      (node (ref "X1") (pin "37") (pinfunction "P$37_37") (pintype "bidirectional"))
    )
    (net (code "292") (name "unconnected-(X1-P$38-Pad38)") (class "Default")
      (node (ref "X1") (pin "38") (pinfunction "P$38_38") (pintype "bidirectional"))
    )
    (net (code "293") (name "unconnected-(X1-P$40-Pad40)") (class "Default")
      (node (ref "X1") (pin "40") (pinfunction "P$40_40") (pintype "bidirectional"))
    )
    (net (code "294") (name "unconnected-(X2-Pad1)") (class "Default")
      (node (ref "X2") (pin "1") (pinfunction "1_1") (pintype "passive"))
    )
    (net (code "295") (name "unconnected-(X2AA-1-Pad33)") (class "Default")
      (node (ref "X2") (pin "33") (pinfunction "1_33") (pintype "passive"))
    )
    (net (code "296") (name "unconnected-(X2AB-1-Pad34)") (class "Default")
      (node (ref "X2") (pin "34") (pinfunction "1_34") (pintype "passive"))
    )
    (net (code "297") (name "unconnected-(X2AC-1-Pad35)") (class "Default")
      (node (ref "X2") (pin "35") (pinfunction "1_35") (pintype "passive"))
    )
    (net (code "298") (name "unconnected-(X2AD-1-Pad36)") (class "Default")
      (node (ref "X2") (pin "36") (pinfunction "1_36") (pintype "passive"))
    )
    (net (code "299") (name "unconnected-(X2AE-1-Pad37)") (class "Default")
      (node (ref "X2") (pin "37") (pinfunction "1_37") (pintype "passive"))
    )
    (net (code "300") (name "unconnected-(X2AF-1-Pad38)") (class "Default")
      (node (ref "X2") (pin "38") (pinfunction "1_38") (pintype "passive"))
    )
    (net (code "301") (name "unconnected-(X2AG-1-Pad39)") (class "Default")
      (node (ref "X2") (pin "39") (pinfunction "1_39") (pintype "passive"))
    )
    (net (code "302") (name "unconnected-(X2AH-1-Pad4)") (class "Default")
      (node (ref "X2") (pin "4") (pinfunction "1_4") (pintype "passive"))
    )
    (net (code "303") (name "unconnected-(X2AI-1-Pad40)") (class "Default")
      (node (ref "X2") (pin "40") (pinfunction "1_40") (pintype "passive"))
    )
    (net (code "304") (name "unconnected-(X2AJ-1-Pad5)") (class "Default")
      (node (ref "X2") (pin "5") (pinfunction "1_5") (pintype "passive"))
    )
    (net (code "305") (name "unconnected-(X2AK-1-Pad6)") (class "Default")
      (node (ref "X2") (pin "6") (pinfunction "1_6") (pintype "passive"))
    )
    (net (code "306") (name "unconnected-(X2AL-1-Pad7)") (class "Default")
      (node (ref "X2") (pin "7") (pinfunction "1_7") (pintype "passive"))
    )
    (net (code "307") (name "unconnected-(X2AM-1-Pad8)") (class "Default")
      (node (ref "X2") (pin "8") (pinfunction "1_8") (pintype "passive"))
    )
    (net (code "308") (name "unconnected-(X2AN-1-Pad9)") (class "Default")
      (node (ref "X2") (pin "9") (pinfunction "1_9") (pintype "passive"))
    )
    (net (code "309") (name "unconnected-(X2B-1-Pad10)") (class "Default")
      (node (ref "X2") (pin "10") (pinfunction "1_10") (pintype "passive"))
    )
    (net (code "310") (name "unconnected-(X2C-1-Pad11)") (class "Default")
      (node (ref "X2") (pin "11") (pinfunction "1_11") (pintype "passive"))
    )
    (net (code "311") (name "unconnected-(X2D-1-Pad12)") (class "Default")
      (node (ref "X2") (pin "12") (pinfunction "1_12") (pintype "passive"))
    )
    (net (code "312") (name "unconnected-(X2E-1-Pad13)") (class "Default")
      (node (ref "X2") (pin "13") (pinfunction "1_13") (pintype "passive"))
    )
    (net (code "313") (name "unconnected-(X2F-1-Pad14)") (class "Default")
      (node (ref "X2") (pin "14") (pinfunction "1_14") (pintype "passive"))
    )
    (net (code "314") (name "unconnected-(X2G-1-Pad15)") (class "Default")
      (node (ref "X2") (pin "15") (pinfunction "1_15") (pintype "passive"))
    )
    (net (code "315") (name "unconnected-(X2H-1-Pad16)") (class "Default")
      (node (ref "X2") (pin "16") (pinfunction "1_16") (pintype "passive"))
    )
    (net (code "316") (name "unconnected-(X2I-1-Pad17)") (class "Default")
      (node (ref "X2") (pin "17") (pinfunction "1_17") (pintype "passive"))
    )
    (net (code "317") (name "unconnected-(X2J-1-Pad18)") (class "Default")
      (node (ref "X2") (pin "18") (pinfunction "1_18") (pintype "passive"))
    )
    (net (code "318") (name "unconnected-(X2K-1-Pad19)") (class "Default")
      (node (ref "X2") (pin "19") (pinfunction "1_19") (pintype "passive"))
    )
    (net (code "319") (name "unconnected-(X2L-1-Pad2)") (class "Default")
      (node (ref "X2") (pin "2") (pinfunction "1_2") (pintype "passive"))
    )
    (net (code "320") (name "unconnected-(X2M-1-Pad20)") (class "Default")
      (node (ref "X2") (pin "20") (pinfunction "1_20") (pintype "passive"))
    )
    (net (code "321") (name "unconnected-(X2N-1-Pad21)") (class "Default")
      (node (ref "X2") (pin "21") (pinfunction "1_21") (pintype "passive"))
    )
    (net (code "322") (name "unconnected-(X2O-1-Pad22)") (class "Default")
      (node (ref "X2") (pin "22") (pinfunction "1_22") (pintype "passive"))
    )
    (net (code "323") (name "unconnected-(X2P-1-Pad23)") (class "Default")
      (node (ref "X2") (pin "23") (pinfunction "1_23") (pintype "passive"))
    )
    (net (code "324") (name "unconnected-(X2Q-1-Pad24)") (class "Default")
      (node (ref "X2") (pin "24") (pinfunction "1_24") (pintype "passive"))
    )
    (net (code "325") (name "unconnected-(X2R-1-Pad25)") (class "Default")
      (node (ref "X2") (pin "25") (pinfunction "1_25") (pintype "passive"))
    )
    (net (code "326") (name "unconnected-(X2S-1-Pad26)") (class "Default")
      (node (ref "X2") (pin "26") (pinfunction "1_26") (pintype "passive"))
    )
    (net (code "327") (name "unconnected-(X2T-1-Pad27)") (class "Default")
      (node (ref "X2") (pin "27") (pinfunction "1_27") (pintype "passive"))
    )
    (net (code "328") (name "unconnected-(X2U-1-Pad28)") (class "Default")
      (node (ref "X2") (pin "28") (pinfunction "1_28") (pintype "passive"))
    )
    (net (code "329") (name "unconnected-(X2V-1-Pad29)") (class "Default")
      (node (ref "X2") (pin "29") (pinfunction "1_29") (pintype "passive"))
    )
    (net (code "330") (name "unconnected-(X2W-1-Pad3)") (class "Default")
      (node (ref "X2") (pin "3") (pinfunction "1_3") (pintype "passive"))
    )
    (net (code "331") (name "unconnected-(X2X-1-Pad30)") (class "Default")
      (node (ref "X2") (pin "30") (pinfunction "1_30") (pintype "passive"))
    )
    (net (code "332") (name "unconnected-(X2Y-1-Pad31)") (class "Default")
      (node (ref "X2") (pin "31") (pinfunction "1_31") (pintype "passive"))
    )
    (net (code "333") (name "unconnected-(X2Z-1-Pad32)") (class "Default")
      (node (ref "X2") (pin "32") (pinfunction "1_32") (pintype "passive"))
    )
  )
)
